# MusselGapeTracker_RevB.net
KiCad netlist of a schematic drawn in EAGLE
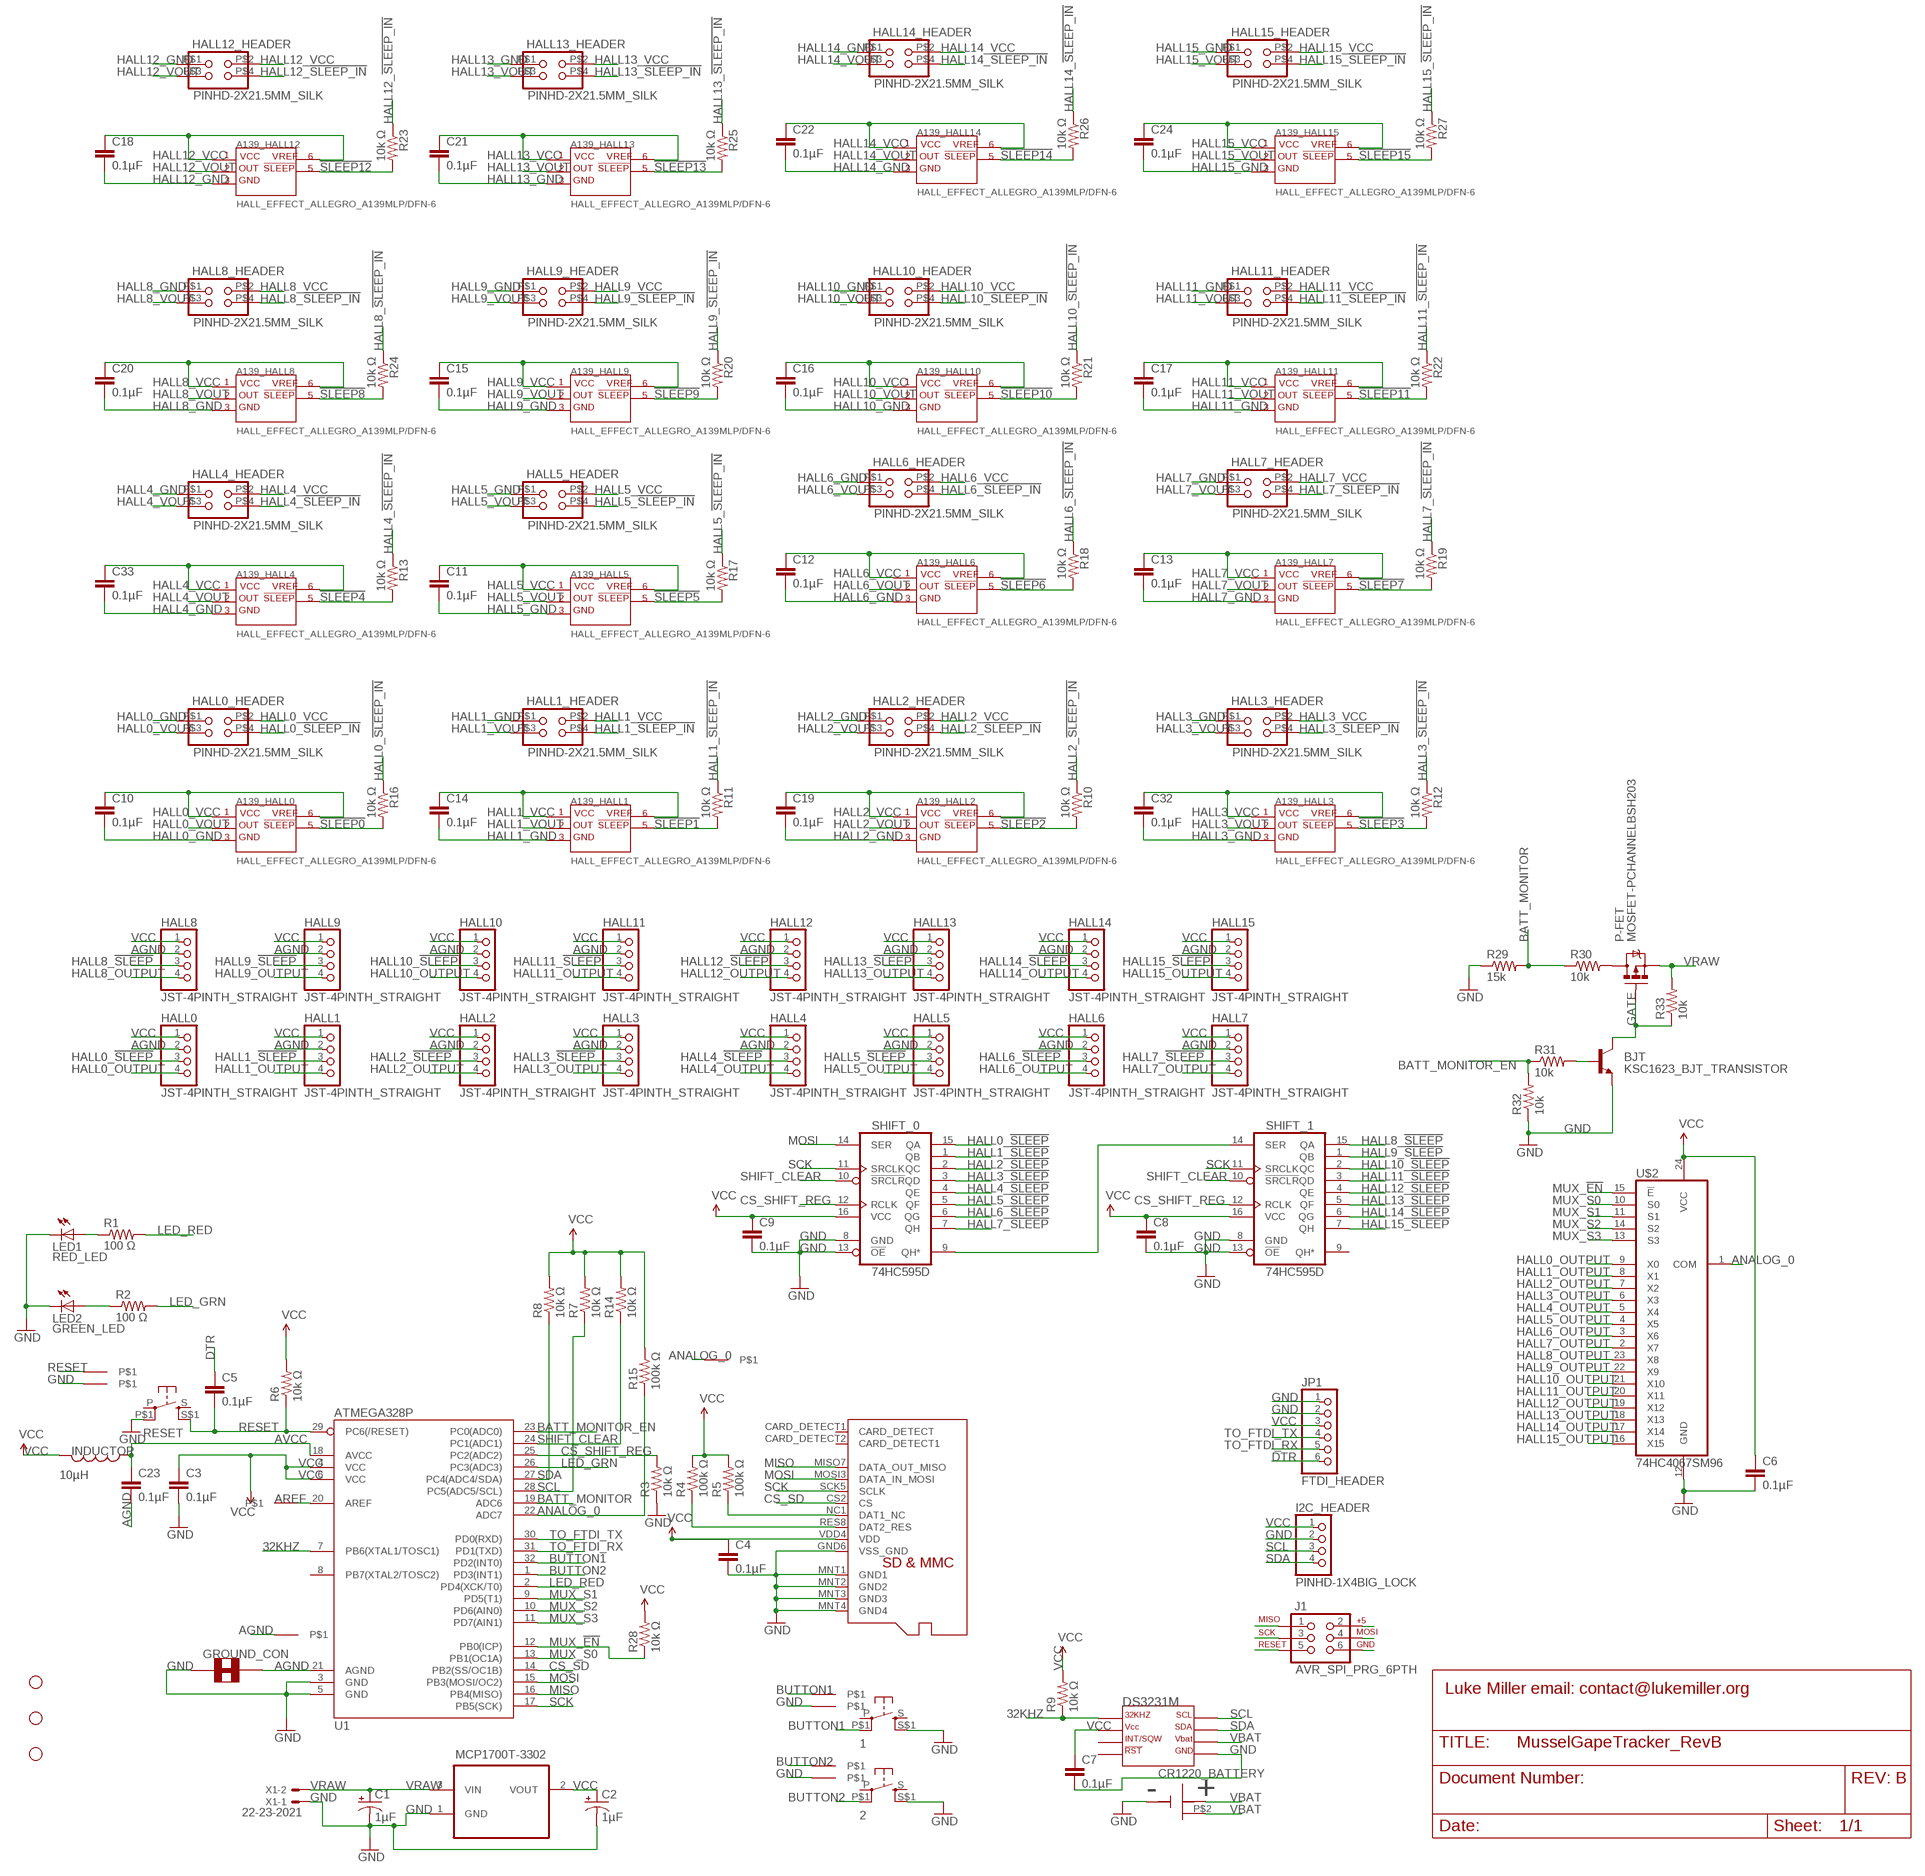
[diagram p0: schematic, sheet 1]

(export (version "E")
  (design (tool "Eeschema 10.0.6"))
  (components
    (comp (ref "1")
      (value "PUSHBUTTON_DPST_SMDSTANDARD")
      (footprint "eagle-import:PUSHBUTTON_DPST_SMD")
      (libsource (lib "eagle-import") (part "PUSHBUTTON_DPST_SMDSTANDARD"))
    )
    (comp (ref "2")
      (value "PUSHBUTTON_DPST_SMDSTANDARD")
      (footprint "eagle-import:PUSHBUTTON_DPST_SMD")
      (libsource (lib "eagle-import") (part "PUSHBUTTON_DPST_SMDSTANDARD"))
    )
    (comp (ref "A139_HALL0")
      (value "HALL_EFFECT_ALLEGRO_A139MLP/DFN-6")
      (footprint "eagle-import:A139__HALL_EFFECT")
      (libsource (lib "eagle-import") (part "HALL_EFFECT_ALLEGRO_A139MLP/DFN-6"))
    )
    (comp (ref "A139_HALL1")
      (value "HALL_EFFECT_ALLEGRO_A139MLP/DFN-6")
      (footprint "eagle-import:A139__HALL_EFFECT")
      (libsource (lib "eagle-import") (part "HALL_EFFECT_ALLEGRO_A139MLP/DFN-6"))
    )
    (comp (ref "A139_HALL2")
      (value "HALL_EFFECT_ALLEGRO_A139MLP/DFN-6")
      (footprint "eagle-import:A139__HALL_EFFECT")
      (libsource (lib "eagle-import") (part "HALL_EFFECT_ALLEGRO_A139MLP/DFN-6"))
    )
    (comp (ref "A139_HALL3")
      (value "HALL_EFFECT_ALLEGRO_A139MLP/DFN-6")
      (footprint "eagle-import:A139__HALL_EFFECT")
      (libsource (lib "eagle-import") (part "HALL_EFFECT_ALLEGRO_A139MLP/DFN-6"))
    )
    (comp (ref "A139_HALL4")
      (value "HALL_EFFECT_ALLEGRO_A139MLP/DFN-6")
      (footprint "eagle-import:A139__HALL_EFFECT")
      (libsource (lib "eagle-import") (part "HALL_EFFECT_ALLEGRO_A139MLP/DFN-6"))
    )
    (comp (ref "A139_HALL5")
      (value "HALL_EFFECT_ALLEGRO_A139MLP/DFN-6")
      (footprint "eagle-import:A139__HALL_EFFECT")
      (libsource (lib "eagle-import") (part "HALL_EFFECT_ALLEGRO_A139MLP/DFN-6"))
    )
    (comp (ref "A139_HALL6")
      (value "HALL_EFFECT_ALLEGRO_A139MLP/DFN-6")
      (footprint "eagle-import:A139__HALL_EFFECT")
      (libsource (lib "eagle-import") (part "HALL_EFFECT_ALLEGRO_A139MLP/DFN-6"))
    )
    (comp (ref "A139_HALL7")
      (value "HALL_EFFECT_ALLEGRO_A139MLP/DFN-6")
      (footprint "eagle-import:A139__HALL_EFFECT")
      (libsource (lib "eagle-import") (part "HALL_EFFECT_ALLEGRO_A139MLP/DFN-6"))
    )
    (comp (ref "A139_HALL8")
      (value "HALL_EFFECT_ALLEGRO_A139MLP/DFN-6")
      (footprint "eagle-import:A139__HALL_EFFECT")
      (libsource (lib "eagle-import") (part "HALL_EFFECT_ALLEGRO_A139MLP/DFN-6"))
    )
    (comp (ref "A139_HALL9")
      (value "HALL_EFFECT_ALLEGRO_A139MLP/DFN-6")
      (footprint "eagle-import:A139__HALL_EFFECT")
      (libsource (lib "eagle-import") (part "HALL_EFFECT_ALLEGRO_A139MLP/DFN-6"))
    )
    (comp (ref "A139_HALL10")
      (value "HALL_EFFECT_ALLEGRO_A139MLP/DFN-6")
      (footprint "eagle-import:A139__HALL_EFFECT")
      (libsource (lib "eagle-import") (part "HALL_EFFECT_ALLEGRO_A139MLP/DFN-6"))
    )
    (comp (ref "A139_HALL11")
      (value "HALL_EFFECT_ALLEGRO_A139MLP/DFN-6")
      (footprint "eagle-import:A139__HALL_EFFECT")
      (libsource (lib "eagle-import") (part "HALL_EFFECT_ALLEGRO_A139MLP/DFN-6"))
    )
    (comp (ref "A139_HALL12")
      (value "HALL_EFFECT_ALLEGRO_A139MLP/DFN-6")
      (footprint "eagle-import:A139__HALL_EFFECT")
      (libsource (lib "eagle-import") (part "HALL_EFFECT_ALLEGRO_A139MLP/DFN-6"))
    )
    (comp (ref "A139_HALL13")
      (value "HALL_EFFECT_ALLEGRO_A139MLP/DFN-6")
      (footprint "eagle-import:A139__HALL_EFFECT")
      (libsource (lib "eagle-import") (part "HALL_EFFECT_ALLEGRO_A139MLP/DFN-6"))
    )
    (comp (ref "A139_HALL14")
      (value "HALL_EFFECT_ALLEGRO_A139MLP/DFN-6")
      (footprint "eagle-import:A139__HALL_EFFECT")
      (libsource (lib "eagle-import") (part "HALL_EFFECT_ALLEGRO_A139MLP/DFN-6"))
    )
    (comp (ref "A139_HALL15")
      (value "HALL_EFFECT_ALLEGRO_A139MLP/DFN-6")
      (footprint "eagle-import:A139__HALL_EFFECT")
      (libsource (lib "eagle-import") (part "HALL_EFFECT_ALLEGRO_A139MLP/DFN-6"))
    )
    (comp (ref "BJT")
      (value "KSC1623_BJT_TRANSISTOR")
      (footprint "eagle-import:SOT23")
      (libsource (lib "eagle-import") (part "KSC1623_BJT_TRANSISTOR"))
    )
    (comp (ref "C1")
      (value "1µF")
      (footprint "eagle-import:PANASONIC_B")
      (libsource (lib "eagle-import") (part "CPOL-USB"))
    )
    (comp (ref "C2")
      (value "1µF")
      (footprint "eagle-import:PANASONIC_B")
      (libsource (lib "eagle-import") (part "CPOL-USB"))
    )
    (comp (ref "C3")
      (value "0.1µF")
      (footprint "eagle-import:0603")
      (libsource (lib "eagle-import") (part "CAP0603"))
    )
    (comp (ref "C4")
      (value "0.1µF")
      (footprint "eagle-import:0603")
      (libsource (lib "eagle-import") (part "CAP0603"))
    )
    (comp (ref "C5")
      (value "0.1µF")
      (footprint "eagle-import:0603")
      (libsource (lib "eagle-import") (part "CAP0603"))
    )
    (comp (ref "C6")
      (value "0.1µF")
      (footprint "eagle-import:0603")
      (libsource (lib "eagle-import") (part "CAP0603"))
    )
    (comp (ref "C7")
      (value "0.1µF")
      (footprint "eagle-import:0603")
      (libsource (lib "eagle-import") (part "CAP0603"))
    )
    (comp (ref "C8")
      (value "0.1µF")
      (footprint "eagle-import:0603")
      (libsource (lib "eagle-import") (part "CAP0603"))
    )
    (comp (ref "C9")
      (value "0.1µF")
      (footprint "eagle-import:0603")
      (libsource (lib "eagle-import") (part "CAP0603"))
    )
    (comp (ref "C10")
      (value "0.1µF")
      (footprint "eagle-import:0603")
      (libsource (lib "eagle-import") (part "CAP0603"))
    )
    (comp (ref "C11")
      (value "0.1µF")
      (footprint "eagle-import:0603")
      (libsource (lib "eagle-import") (part "CAP0603"))
    )
    (comp (ref "C12")
      (value "0.1µF")
      (footprint "eagle-import:0603")
      (libsource (lib "eagle-import") (part "CAP0603"))
    )
    (comp (ref "C13")
      (value "0.1µF")
      (footprint "eagle-import:0603")
      (libsource (lib "eagle-import") (part "CAP0603"))
    )
    (comp (ref "C14")
      (value "0.1µF")
      (footprint "eagle-import:0603")
      (libsource (lib "eagle-import") (part "CAP0603"))
    )
    (comp (ref "C15")
      (value "0.1µF")
      (footprint "eagle-import:0603")
      (libsource (lib "eagle-import") (part "CAP0603"))
    )
    (comp (ref "C16")
      (value "0.1µF")
      (footprint "eagle-import:0603")
      (libsource (lib "eagle-import") (part "CAP0603"))
    )
    (comp (ref "C17")
      (value "0.1µF")
      (footprint "eagle-import:0603")
      (libsource (lib "eagle-import") (part "CAP0603"))
    )
    (comp (ref "C18")
      (value "0.1µF")
      (footprint "eagle-import:0603")
      (libsource (lib "eagle-import") (part "CAP0603"))
    )
    (comp (ref "C19")
      (value "0.1µF")
      (footprint "eagle-import:0603")
      (libsource (lib "eagle-import") (part "CAP0603"))
    )
    (comp (ref "C20")
      (value "0.1µF")
      (footprint "eagle-import:0603")
      (libsource (lib "eagle-import") (part "CAP0603"))
    )
    (comp (ref "C21")
      (value "0.1µF")
      (footprint "eagle-import:0603")
      (libsource (lib "eagle-import") (part "CAP0603"))
    )
    (comp (ref "C22")
      (value "0.1µF")
      (footprint "eagle-import:0603")
      (libsource (lib "eagle-import") (part "CAP0603"))
    )
    (comp (ref "C23")
      (value "0.1µF")
      (footprint "eagle-import:0603")
      (libsource (lib "eagle-import") (part "CAP0603"))
    )
    (comp (ref "C24")
      (value "0.1µF")
      (footprint "eagle-import:0603")
      (libsource (lib "eagle-import") (part "CAP0603"))
    )
    (comp (ref "C32")
      (value "0.1µF")
      (footprint "eagle-import:0603")
      (libsource (lib "eagle-import") (part "CAP0603"))
    )
    (comp (ref "C33")
      (value "0.1µF")
      (footprint "eagle-import:0603")
      (libsource (lib "eagle-import") (part "CAP0603"))
    )
    (comp (ref "CR1220_BATTERY")
      (value "CR1220_BATTERY_HOLDERSMD")
      (footprint "eagle-import:CR1220_BATTERY_HOLDER_SMD")
      (libsource (lib "eagle-import") (part "CR1220_BATTERY_HOLDERSMD"))
    )
    (comp (ref "DS3231M")
      (value "DS3231MSOIC-8")
      (footprint "eagle-import:DS3231M_SOIC8")
      (libsource (lib "eagle-import") (part "DS3231MSOIC-8"))
    )
    (comp (ref "GROUND_CON")
      (value "SOLDER_JUMPER_TRACESTANDARD")
      (footprint "eagle-import:SJ_2S-TRACE")
      (libsource (lib "eagle-import") (part "SOLDER_JUMPER_TRACESTANDARD"))
    )
    (comp (ref "HALL0")
      (value "JST-4PINTH_STRAIGHT")
      (footprint "eagle-import:JST-PH-4-THM")
      (libsource (lib "eagle-import") (part "JST-4PINTH_STRAIGHT"))
    )
    (comp (ref "HALL0_HEADER")
      (value "PINHD-2X21.5MM_SILK")
      (footprint "eagle-import:2X2_1.5MM")
      (libsource (lib "eagle-import") (part "PINHD-2X21.5MM_SILK"))
    )
    (comp (ref "HALL1")
      (value "JST-4PINTH_STRAIGHT")
      (footprint "eagle-import:JST-PH-4-THM")
      (libsource (lib "eagle-import") (part "JST-4PINTH_STRAIGHT"))
    )
    (comp (ref "HALL1_HEADER")
      (value "PINHD-2X21.5MM_SILK")
      (footprint "eagle-import:2X2_1.5MM")
      (libsource (lib "eagle-import") (part "PINHD-2X21.5MM_SILK"))
    )
    (comp (ref "HALL2")
      (value "JST-4PINTH_STRAIGHT")
      (footprint "eagle-import:JST-PH-4-THM")
      (libsource (lib "eagle-import") (part "JST-4PINTH_STRAIGHT"))
    )
    (comp (ref "HALL2_HEADER")
      (value "PINHD-2X21.5MM_SILK")
      (footprint "eagle-import:2X2_1.5MM")
      (libsource (lib "eagle-import") (part "PINHD-2X21.5MM_SILK"))
    )
    (comp (ref "HALL3")
      (value "JST-4PINTH_STRAIGHT")
      (footprint "eagle-import:JST-PH-4-THM")
      (libsource (lib "eagle-import") (part "JST-4PINTH_STRAIGHT"))
    )
    (comp (ref "HALL3_HEADER")
      (value "PINHD-2X21.5MM_SILK")
      (footprint "eagle-import:2X2_1.5MM")
      (libsource (lib "eagle-import") (part "PINHD-2X21.5MM_SILK"))
    )
    (comp (ref "HALL4")
      (value "JST-4PINTH_STRAIGHT")
      (footprint "eagle-import:JST-PH-4-THM")
      (libsource (lib "eagle-import") (part "JST-4PINTH_STRAIGHT"))
    )
    (comp (ref "HALL4_HEADER")
      (value "PINHD-2X21.5MM_SILK")
      (footprint "eagle-import:2X2_1.5MM")
      (libsource (lib "eagle-import") (part "PINHD-2X21.5MM_SILK"))
    )
    (comp (ref "HALL5")
      (value "JST-4PINTH_STRAIGHT")
      (footprint "eagle-import:JST-PH-4-THM")
      (libsource (lib "eagle-import") (part "JST-4PINTH_STRAIGHT"))
    )
    (comp (ref "HALL5_HEADER")
      (value "PINHD-2X21.5MM_SILK")
      (footprint "eagle-import:2X2_1.5MM")
      (libsource (lib "eagle-import") (part "PINHD-2X21.5MM_SILK"))
    )
    (comp (ref "HALL6")
      (value "JST-4PINTH_STRAIGHT")
      (footprint "eagle-import:JST-PH-4-THM")
      (libsource (lib "eagle-import") (part "JST-4PINTH_STRAIGHT"))
    )
    (comp (ref "HALL6_HEADER")
      (value "PINHD-2X21.5MM_SILK")
      (footprint "eagle-import:2X2_1.5MM")
      (libsource (lib "eagle-import") (part "PINHD-2X21.5MM_SILK"))
    )
    (comp (ref "HALL7")
      (value "JST-4PINTH_STRAIGHT")
      (footprint "eagle-import:JST-PH-4-THM")
      (libsource (lib "eagle-import") (part "JST-4PINTH_STRAIGHT"))
    )
    (comp (ref "HALL7_HEADER")
      (value "PINHD-2X21.5MM_SILK")
      (footprint "eagle-import:2X2_1.5MM")
      (libsource (lib "eagle-import") (part "PINHD-2X21.5MM_SILK"))
    )
    (comp (ref "HALL8")
      (value "JST-4PINTH_STRAIGHT")
      (footprint "eagle-import:JST-PH-4-THM")
      (libsource (lib "eagle-import") (part "JST-4PINTH_STRAIGHT"))
    )
    (comp (ref "HALL8_HEADER")
      (value "PINHD-2X21.5MM_SILK")
      (footprint "eagle-import:2X2_1.5MM")
      (libsource (lib "eagle-import") (part "PINHD-2X21.5MM_SILK"))
    )
    (comp (ref "HALL9")
      (value "JST-4PINTH_STRAIGHT")
      (footprint "eagle-import:JST-PH-4-THM")
      (libsource (lib "eagle-import") (part "JST-4PINTH_STRAIGHT"))
    )
    (comp (ref "HALL9_HEADER")
      (value "PINHD-2X21.5MM_SILK")
      (footprint "eagle-import:2X2_1.5MM")
      (libsource (lib "eagle-import") (part "PINHD-2X21.5MM_SILK"))
    )
    (comp (ref "HALL10")
      (value "JST-4PINTH_STRAIGHT")
      (footprint "eagle-import:JST-PH-4-THM")
      (libsource (lib "eagle-import") (part "JST-4PINTH_STRAIGHT"))
    )
    (comp (ref "HALL10_HEADER")
      (value "PINHD-2X21.5MM_SILK")
      (footprint "eagle-import:2X2_1.5MM")
      (libsource (lib "eagle-import") (part "PINHD-2X21.5MM_SILK"))
    )
    (comp (ref "HALL11")
      (value "JST-4PINTH_STRAIGHT")
      (footprint "eagle-import:JST-PH-4-THM")
      (libsource (lib "eagle-import") (part "JST-4PINTH_STRAIGHT"))
    )
    (comp (ref "HALL11_HEADER")
      (value "PINHD-2X21.5MM_SILK")
      (footprint "eagle-import:2X2_1.5MM")
      (libsource (lib "eagle-import") (part "PINHD-2X21.5MM_SILK"))
    )
    (comp (ref "HALL12")
      (value "JST-4PINTH_STRAIGHT")
      (footprint "eagle-import:JST-PH-4-THM")
      (libsource (lib "eagle-import") (part "JST-4PINTH_STRAIGHT"))
    )
    (comp (ref "HALL12_HEADER")
      (value "PINHD-2X21.5MM_SILK")
      (footprint "eagle-import:2X2_1.5MM")
      (libsource (lib "eagle-import") (part "PINHD-2X21.5MM_SILK"))
    )
    (comp (ref "HALL13")
      (value "JST-4PINTH_STRAIGHT")
      (footprint "eagle-import:JST-PH-4-THM")
      (libsource (lib "eagle-import") (part "JST-4PINTH_STRAIGHT"))
    )
    (comp (ref "HALL13_HEADER")
      (value "PINHD-2X21.5MM_SILK")
      (footprint "eagle-import:2X2_1.5MM")
      (libsource (lib "eagle-import") (part "PINHD-2X21.5MM_SILK"))
    )
    (comp (ref "HALL14")
      (value "JST-4PINTH_STRAIGHT")
      (footprint "eagle-import:JST-PH-4-THM")
      (libsource (lib "eagle-import") (part "JST-4PINTH_STRAIGHT"))
    )
    (comp (ref "HALL14_HEADER")
      (value "PINHD-2X21.5MM_SILK")
      (footprint "eagle-import:2X2_1.5MM")
      (libsource (lib "eagle-import") (part "PINHD-2X21.5MM_SILK"))
    )
    (comp (ref "HALL15")
      (value "JST-4PINTH_STRAIGHT")
      (footprint "eagle-import:JST-PH-4-THM")
      (libsource (lib "eagle-import") (part "JST-4PINTH_STRAIGHT"))
    )
    (comp (ref "HALL15_HEADER")
      (value "PINHD-2X21.5MM_SILK")
      (footprint "eagle-import:2X2_1.5MM")
      (libsource (lib "eagle-import") (part "PINHD-2X21.5MM_SILK"))
    )
    (comp (ref "I2C_HEADER")
      (value "PINHD-1X4BIG_LOCK")
      (footprint "eagle-import:1X04_BIGLOCK")
      (libsource (lib "eagle-import") (part "PINHD-1X4BIG_LOCK"))
    )
    (comp (ref "INDUCTOR")
      (value "10µH")
      (footprint "eagle-import:I_0805")
      (libsource (lib "eagle-import") (part "INDUCTOR0805_TY"))
    )
    (comp (ref "J1")
      (value "AVR_SPI_PRG_6PTH")
      (footprint "eagle-import:2X3")
      (libsource (lib "eagle-import") (part "AVR_SPI_PRG_6PTH"))
    )
    (comp (ref "JP1")
      (value "FTDI_HEADER")
      (footprint "eagle-import:1X06-BIGLOCK")
      (libsource (lib "eagle-import") (part "PINHD-1X6LOCK"))
    )
    (comp (ref "LED1")
      (value "RED_LED")
      (footprint "eagle-import:CHIPLED_0805")
      (libsource (lib "eagle-import") (part "LED0805"))
    )
    (comp (ref "LED2")
      (value "GREEN_LED")
      (footprint "eagle-import:CHIPLED_0805")
      (libsource (lib "eagle-import") (part "LED0805"))
    )
    (comp (ref "MCP1700T-3302")
      (value "MCP1700T-3302E/TT")
      (footprint "eagle-import:SOT95P237X112-3N")
      (libsource (lib "eagle-import") (part "MCP1700T-3302E/TT"))
    )
    (comp (ref "P-FET")
      (value "MOSFET-PCHANNELBSH203")
      (footprint "eagle-import:SOT23-3")
      (libsource (lib "eagle-import") (part "MOSFET-PCHANNELBSH203"))
    )
    (comp (ref "R1")
      (value "100 Ω")
      (footprint "eagle-import:R0603")
      (libsource (lib "eagle-import") (part "RESISTOR_SMDR0603"))
    )
    (comp (ref "R2")
      (value "100 Ω")
      (footprint "eagle-import:R0603")
      (libsource (lib "eagle-import") (part "RESISTOR_SMDR0603"))
    )
    (comp (ref "R3")
      (value "10k Ω")
      (footprint "eagle-import:R0603")
      (libsource (lib "eagle-import") (part "RESISTOR_SMDR0603"))
    )
    (comp (ref "R4")
      (value "100k Ω")
      (footprint "eagle-import:R0603")
      (libsource (lib "eagle-import") (part "RESISTOR_SMDR0603"))
    )
    (comp (ref "R5")
      (value "100k Ω")
      (footprint "eagle-import:R0603")
      (libsource (lib "eagle-import") (part "RESISTOR_SMDR0603"))
    )
    (comp (ref "R6")
      (value "10k Ω")
      (footprint "eagle-import:R0603")
      (libsource (lib "eagle-import") (part "RESISTOR_SMDR0603"))
    )
    (comp (ref "R7")
      (value "10k Ω")
      (footprint "eagle-import:R0603")
      (libsource (lib "eagle-import") (part "RESISTOR_SMDR0603"))
    )
    (comp (ref "R8")
      (value "10k Ω")
      (footprint "eagle-import:R0603")
      (libsource (lib "eagle-import") (part "RESISTOR_SMDR0603"))
    )
    (comp (ref "R9")
      (value "10k Ω")
      (footprint "eagle-import:R0603")
      (libsource (lib "eagle-import") (part "RESISTOR_SMDR0603"))
    )
    (comp (ref "R10")
      (value "10k Ω")
      (footprint "eagle-import:R0603")
      (libsource (lib "eagle-import") (part "RESISTOR_SMDR0603"))
    )
    (comp (ref "R11")
      (value "10k Ω")
      (footprint "eagle-import:R0603")
      (libsource (lib "eagle-import") (part "RESISTOR_SMDR0603"))
    )
    (comp (ref "R12")
      (value "10k Ω")
      (footprint "eagle-import:R0603")
      (libsource (lib "eagle-import") (part "RESISTOR_SMDR0603"))
    )
    (comp (ref "R13")
      (value "10k Ω")
      (footprint "eagle-import:R0603")
      (libsource (lib "eagle-import") (part "RESISTOR_SMDR0603"))
    )
    (comp (ref "R14")
      (value "10k Ω")
      (footprint "eagle-import:R0603")
      (libsource (lib "eagle-import") (part "RESISTOR_SMDR0603"))
    )
    (comp (ref "R15")
      (value "100k Ω")
      (footprint "eagle-import:R0603")
      (libsource (lib "eagle-import") (part "RESISTOR_SMDR0603"))
    )
    (comp (ref "R16")
      (value "10k Ω")
      (footprint "eagle-import:R0603")
      (libsource (lib "eagle-import") (part "RESISTOR_SMDR0603"))
    )
    (comp (ref "R17")
      (value "10k Ω")
      (footprint "eagle-import:R0603")
      (libsource (lib "eagle-import") (part "RESISTOR_SMDR0603"))
    )
    (comp (ref "R18")
      (value "10k Ω")
      (footprint "eagle-import:R0603")
      (libsource (lib "eagle-import") (part "RESISTOR_SMDR0603"))
    )
    (comp (ref "R19")
      (value "10k Ω")
      (footprint "eagle-import:R0603")
      (libsource (lib "eagle-import") (part "RESISTOR_SMDR0603"))
    )
    (comp (ref "R20")
      (value "10k Ω")
      (footprint "eagle-import:R0603")
      (libsource (lib "eagle-import") (part "RESISTOR_SMDR0603"))
    )
    (comp (ref "R21")
      (value "10k Ω")
      (footprint "eagle-import:R0603")
      (libsource (lib "eagle-import") (part "RESISTOR_SMDR0603"))
    )
    (comp (ref "R22")
      (value "10k Ω")
      (footprint "eagle-import:R0603")
      (libsource (lib "eagle-import") (part "RESISTOR_SMDR0603"))
    )
    (comp (ref "R23")
      (value "10k Ω")
      (footprint "eagle-import:R0603")
      (libsource (lib "eagle-import") (part "RESISTOR_SMDR0603"))
    )
    (comp (ref "R24")
      (value "10k Ω")
      (footprint "eagle-import:R0603")
      (libsource (lib "eagle-import") (part "RESISTOR_SMDR0603"))
    )
    (comp (ref "R25")
      (value "10k Ω")
      (footprint "eagle-import:R0603")
      (libsource (lib "eagle-import") (part "RESISTOR_SMDR0603"))
    )
    (comp (ref "R26")
      (value "10k Ω")
      (footprint "eagle-import:R0603")
      (libsource (lib "eagle-import") (part "RESISTOR_SMDR0603"))
    )
    (comp (ref "R27")
      (value "10k Ω")
      (footprint "eagle-import:R0603")
      (libsource (lib "eagle-import") (part "RESISTOR_SMDR0603"))
    )
    (comp (ref "R28")
      (value "10k Ω")
      (footprint "eagle-import:R0603")
      (libsource (lib "eagle-import") (part "RESISTOR_SMDR0603"))
    )
    (comp (ref "R29")
      (value "15k")
      (footprint "eagle-import:R0603")
      (libsource (lib "eagle-import") (part "RESISTOR_SMDR0603"))
    )
    (comp (ref "R30")
      (value "10k")
      (footprint "eagle-import:R0603")
      (libsource (lib "eagle-import") (part "RESISTOR_SMDR0603"))
    )
    (comp (ref "R31")
      (value "10k")
      (footprint "eagle-import:R0603")
      (libsource (lib "eagle-import") (part "RESISTOR_SMDR0603"))
    )
    (comp (ref "R32")
      (value "10k")
      (footprint "eagle-import:R0603")
      (libsource (lib "eagle-import") (part "RESISTOR_SMDR0603"))
    )
    (comp (ref "R33")
      (value "10k")
      (footprint "eagle-import:R0603")
      (libsource (lib "eagle-import") (part "RESISTOR_SMDR0603"))
    )
    (comp (ref "RESET")
      (value "PUSHBUTTON_DPST_SMDSTANDARD")
      (footprint "eagle-import:PUSHBUTTON_DPST_SMD")
      (libsource (lib "eagle-import") (part "PUSHBUTTON_DPST_SMDSTANDARD"))
    )
    (comp (ref "SHIFT_0")
      (value "74HC595D")
      (footprint "eagle-import:SO16")
      (libsource (lib "eagle-import") (part "74HC595D"))
    )
    (comp (ref "SHIFT_1")
      (value "74HC595D")
      (footprint "eagle-import:SO16")
      (libsource (lib "eagle-import") (part "74HC595D"))
    )
    (comp (ref "STANDOFF1")
      (value "STAND-OFF")
      (footprint "eagle-import:STAND-OFF")
      (libsource (lib "eagle-import") (part "STAND-OFF"))
    )
    (comp (ref "STANDOFF2")
      (value "STAND-OFF")
      (footprint "eagle-import:STAND-OFF")
      (libsource (lib "eagle-import") (part "STAND-OFF"))
    )
    (comp (ref "STANDOFF3")
      (value "STAND-OFF")
      (footprint "eagle-import:STAND-OFF")
      (libsource (lib "eagle-import") (part "STAND-OFF"))
    )
    (comp (ref "U$1")
      (value "MICROSD_MOLEX_REVERSECURRENT")
      (footprint "eagle-import:MICROSD_SOCKET_MOLEX_REVERSEMOUNT")
      (libsource (lib "eagle-import") (part "MICROSD_MOLEX_REVERSECURRENT"))
    )
    (comp (ref "U$2")
      (value "74HC4067SM96")
      (footprint "eagle-import:SSOP24")
      (libsource (lib "eagle-import") (part "74HC4067SM96"))
    )
    (comp (ref "U$3")
      (value "PINHD-1X1SMALL")
      (footprint "eagle-import:1X01_SMALL")
      (libsource (lib "eagle-import") (part "PINHD-1X1SMALL"))
    )
    (comp (ref "U$4")
      (value "PINHD-1X1SMALL")
      (footprint "eagle-import:1X01_SMALL")
      (libsource (lib "eagle-import") (part "PINHD-1X1SMALL"))
    )
    (comp (ref "U$6")
      (value "PINHD-1X1SMALL")
      (footprint "eagle-import:1X01_SMALL")
      (libsource (lib "eagle-import") (part "PINHD-1X1SMALL"))
    )
    (comp (ref "U$7")
      (value "PINHD-1X1SMALL")
      (footprint "eagle-import:1X01_SMALL")
      (libsource (lib "eagle-import") (part "PINHD-1X1SMALL"))
    )
    (comp (ref "U$8")
      (value "PINHD-1X1SMALL")
      (footprint "eagle-import:1X01_SMALL")
      (libsource (lib "eagle-import") (part "PINHD-1X1SMALL"))
    )
    (comp (ref "U$9")
      (value "PINHD-1X1SMALL")
      (footprint "eagle-import:1X01_SMALL")
      (libsource (lib "eagle-import") (part "PINHD-1X1SMALL"))
    )
    (comp (ref "U$10")
      (value "PINHD-1X1SMALL")
      (footprint "eagle-import:1X01_SMALL")
      (libsource (lib "eagle-import") (part "PINHD-1X1SMALL"))
    )
    (comp (ref "U$11")
      (value "PINHD-1X1SMALL")
      (footprint "eagle-import:1X01_SMALL")
      (libsource (lib "eagle-import") (part "PINHD-1X1SMALL"))
    )
    (comp (ref "U$17")
      (value "PINHD-1X1SMALL")
      (footprint "eagle-import:1X01_SMALL")
      (libsource (lib "eagle-import") (part "PINHD-1X1SMALL"))
    )
    (comp (ref "U1")
      (value "ATMEGA328P")
      (footprint "eagle-import:TQFP32-08")
      (libsource (lib "eagle-import") (part "ATMEGA328_SMT"))
    )
    (comp (ref "X1")
      (value "22-23-2021")
      (footprint "eagle-import:22-23-2021")
      (fields (field (name "MF") "MOLEX"))
      (libsource (lib "eagle-import") (part "22-23-2021"))
    )
  )
  (nets
    (net (code "1") (name "/32KHZ") (class "Default")
      (node (ref "DS3231M") (pin "1") (pinfunction "P$1_32KHZ_1") (pintype "bidirectional"))
      (node (ref "R9") (pin "1") (pinfunction "1_1") (pintype "passive"))
      (node (ref "U1") (pin "7") (pinfunction "PB6(XTAL1/TOSC1)_7") (pintype "bidirectional"))
    )
    (net (code "2") (name "/AGND") (class "Default")
      (node (ref "C23") (pin "2") (pinfunction "2_2") (pintype "passive"))
      (node (ref "GROUND_CON") (pin "2") (pinfunction "P$2_2") (pintype "bidirectional"))
      (node (ref "HALL0") (pin "2") (pinfunction "2_2") (pintype "passive"))
      (node (ref "HALL1") (pin "2") (pinfunction "2_2") (pintype "passive"))
      (node (ref "HALL10") (pin "2") (pinfunction "2_2") (pintype "passive"))
      (node (ref "HALL11") (pin "2") (pinfunction "2_2") (pintype "passive"))
      (node (ref "HALL12") (pin "2") (pinfunction "2_2") (pintype "passive"))
      (node (ref "HALL13") (pin "2") (pinfunction "2_2") (pintype "passive"))
      (node (ref "HALL14") (pin "2") (pinfunction "2_2") (pintype "passive"))
      (node (ref "HALL15") (pin "2") (pinfunction "2_2") (pintype "passive"))
      (node (ref "HALL2") (pin "2") (pinfunction "2_2") (pintype "passive"))
      (node (ref "HALL3") (pin "2") (pinfunction "2_2") (pintype "passive"))
      (node (ref "HALL4") (pin "2") (pinfunction "2_2") (pintype "passive"))
      (node (ref "HALL5") (pin "2") (pinfunction "2_2") (pintype "passive"))
      (node (ref "HALL6") (pin "2") (pinfunction "2_2") (pintype "passive"))
      (node (ref "HALL7") (pin "2") (pinfunction "2_2") (pintype "passive"))
      (node (ref "HALL8") (pin "2") (pinfunction "2_2") (pintype "passive"))
      (node (ref "HALL9") (pin "2") (pinfunction "2_2") (pintype "passive"))
      (node (ref "U$11") (pin "1") (pinfunction "P$1_1") (pintype "bidirectional"))
      (node (ref "U1") (pin "21") (pinfunction "AGND_21") (pintype "bidirectional"))
    )
    (net (code "3") (name "/ANALOG_0") (class "Default")
      (node (ref "R15") (pin "1") (pinfunction "1_1") (pintype "passive"))
      (node (ref "U$10") (pin "1") (pinfunction "P$1_1") (pintype "bidirectional"))
      (node (ref "U$2") (pin "1") (pinfunction "COM_1") (pintype "output"))
      (node (ref "U1") (pin "22") (pinfunction "ADC7_22") (pintype "bidirectional"))
    )
    (net (code "4") (name "/AREF") (class "Default")
      (node (ref "U$17") (pin "1") (pinfunction "P$1_1") (pintype "bidirectional"))
      (node (ref "U1") (pin "20") (pinfunction "AREF_20") (pintype "bidirectional"))
    )
    (net (code "5") (name "/AVCC") (class "Default")
      (node (ref "C23") (pin "1") (pinfunction "1_1") (pintype "passive"))
      (node (ref "INDUCTOR") (pin "P$1") (pinfunction "1_P$1") (pintype "passive"))
      (node (ref "U1") (pin "18") (pinfunction "AVCC_18") (pintype "bidirectional"))
    )
    (net (code "6") (name "/BATT_MONITOR") (class "Default")
      (node (ref "R29") (pin "2") (pinfunction "2_2") (pintype "passive"))
      (node (ref "R30") (pin "1") (pinfunction "1_1") (pintype "passive"))
      (node (ref "U1") (pin "19") (pinfunction "ADC6_19") (pintype "bidirectional"))
    )
    (net (code "7") (name "/BATT_MONITOR_EN") (class "Default")
      (node (ref "R31") (pin "1") (pinfunction "1_1") (pintype "passive"))
      (node (ref "R32") (pin "2") (pinfunction "2_2") (pintype "passive"))
      (node (ref "U1") (pin "23") (pinfunction "PC0(ADC0)_23") (pintype "bidirectional"))
    )
    (net (code "8") (name "/BUTTON1") (class "Default")
      (node (ref "1") (pin "P$1") (pinfunction "P1_P$1") (pintype "passive"))
      (node (ref "U$6") (pin "1") (pinfunction "P$1_1") (pintype "bidirectional"))
      (node (ref "U1") (pin "32") (pinfunction "PD2(INT0)_32") (pintype "bidirectional"))
    )
    (net (code "9") (name "/BUTTON2") (class "Default")
      (node (ref "2") (pin "P$1") (pinfunction "P1_P$1") (pintype "passive"))
      (node (ref "U$8") (pin "1") (pinfunction "P$1_1") (pintype "bidirectional"))
      (node (ref "U1") (pin "1") (pinfunction "PD3(INT1)_1") (pintype "bidirectional"))
    )
    (net (code "10") (name "/CS_SD") (class "Default")
      (node (ref "U$1") (pin "CS2") (pinfunction "CS_CS2") (pintype "input"))
      (node (ref "U1") (pin "14") (pinfunction "PB2(SS/OC1B)_14") (pintype "bidirectional"))
    )
    (net (code "11") (name "/CS_SHIFT_REG") (class "Default")
      (node (ref "R3") (pin "2") (pinfunction "2_2") (pintype "passive"))
      (node (ref "SHIFT_0") (pin "12") (pinfunction "RCLK_12") (pintype "input"))
      (node (ref "SHIFT_1") (pin "12") (pinfunction "RCLK_12") (pintype "input"))
      (node (ref "U1") (pin "25") (pinfunction "PC2(ADC2)_25") (pintype "bidirectional"))
    )
    (net (code "12") (name "/DTR") (class "Default")
      (node (ref "C5") (pin "1") (pinfunction "1_1") (pintype "passive"))
      (node (ref "JP1") (pin "6") (pinfunction "6_6") (pintype "passive"))
    )
    (net (code "13") (name "/GATE") (class "Default")
      (node (ref "BJT") (pin "3") (pinfunction "C_3") (pintype "passive"))
      (node (ref "P-FET") (pin "1") (pinfunction "G_1") (pintype "passive"))
      (node (ref "R33") (pin "1") (pinfunction "1_1") (pintype "passive"))
    )
    (net (code "14") (name "/HALL0_GND") (class "Default")
      (node (ref "A139_HALL0") (pin "P$3_4") (pinfunction "P$3_P$3_4") (pintype "bidirectional"))
      (node (ref "C10") (pin "2") (pinfunction "2_2") (pintype "passive"))
      (node (ref "HALL0_HEADER") (pin "P$1") (pinfunction "1_P$1") (pintype "passive"))
    )
    (net (code "15") (name "/HALL0_OUTPUT") (class "Default")
      (node (ref "HALL0") (pin "4") (pinfunction "4_4") (pintype "passive"))
      (node (ref "U$2") (pin "9") (pinfunction "X0_9") (pintype "input"))
    )
    (net (code "16") (name "/HALL0_VCC") (class "Default")
      (node (ref "A139_HALL0") (pin "P$1") (pinfunction "P$1_P$1") (pintype "bidirectional"))
      (node (ref "A139_HALL0") (pin "P$6") (pinfunction "P$6_P$6") (pintype "bidirectional"))
      (node (ref "C10") (pin "1") (pinfunction "1_1") (pintype "passive"))
      (node (ref "HALL0_HEADER") (pin "P$2") (pinfunction "2_P$2") (pintype "passive"))
    )
    (net (code "17") (name "/HALL0_VOUT") (class "Default")
      (node (ref "A139_HALL0") (pin "P$2") (pinfunction "P$2_P$2") (pintype "bidirectional"))
      (node (ref "HALL0_HEADER") (pin "P$3") (pinfunction "3_P$3") (pintype "passive"))
    )
    (net (code "18") (name "/HALL0_~{SLEEP_IN}") (class "Default")
      (node (ref "HALL0_HEADER") (pin "P$4") (pinfunction "4_P$4") (pintype "passive"))
      (node (ref "R16") (pin "1") (pinfunction "1_1") (pintype "passive"))
    )
    (net (code "19") (name "/HALL0_~{SLEEP}") (class "Default")
      (node (ref "HALL0") (pin "3") (pinfunction "3_3") (pintype "passive"))
      (node (ref "SHIFT_0") (pin "15") (pinfunction "QA_15") (pintype "tri_state"))
    )
    (net (code "20") (name "/HALL1_GND") (class "Default")
      (node (ref "A139_HALL1") (pin "P$3_4") (pinfunction "P$3_P$3_4") (pintype "bidirectional"))
      (node (ref "C14") (pin "2") (pinfunction "2_2") (pintype "passive"))
      (node (ref "HALL1_HEADER") (pin "P$1") (pinfunction "1_P$1") (pintype "passive"))
    )
    (net (code "21") (name "/HALL1_OUTPUT") (class "Default")
      (node (ref "HALL1") (pin "4") (pinfunction "4_4") (pintype "passive"))
      (node (ref "U$2") (pin "8") (pinfunction "X1_8") (pintype "input"))
    )
    (net (code "22") (name "/HALL1_VCC") (class "Default")
      (node (ref "A139_HALL1") (pin "P$1") (pinfunction "P$1_P$1") (pintype "bidirectional"))
      (node (ref "A139_HALL1") (pin "P$6") (pinfunction "P$6_P$6") (pintype "bidirectional"))
      (node (ref "C14") (pin "1") (pinfunction "1_1") (pintype "passive"))
      (node (ref "HALL1_HEADER") (pin "P$2") (pinfunction "2_P$2") (pintype "passive"))
    )
    (net (code "23") (name "/HALL1_VOUT") (class "Default")
      (node (ref "A139_HALL1") (pin "P$2") (pinfunction "P$2_P$2") (pintype "bidirectional"))
      (node (ref "HALL1_HEADER") (pin "P$3") (pinfunction "3_P$3") (pintype "passive"))
    )
    (net (code "24") (name "/HALL1_~{SLEEP_IN}") (class "Default")
      (node (ref "HALL1_HEADER") (pin "P$4") (pinfunction "4_P$4") (pintype "passive"))
      (node (ref "R11") (pin "1") (pinfunction "1_1") (pintype "passive"))
    )
    (net (code "25") (name "/HALL1_~{SLEEP}") (class "Default")
      (node (ref "HALL1") (pin "3") (pinfunction "3_3") (pintype "passive"))
      (node (ref "SHIFT_0") (pin "1") (pinfunction "QB_1") (pintype "tri_state"))
    )
    (net (code "26") (name "/HALL2_GND") (class "Default")
      (node (ref "A139_HALL2") (pin "P$3_4") (pinfunction "P$3_P$3_4") (pintype "bidirectional"))
      (node (ref "C19") (pin "2") (pinfunction "2_2") (pintype "passive"))
      (node (ref "HALL2_HEADER") (pin "P$1") (pinfunction "1_P$1") (pintype "passive"))
    )
    (net (code "27") (name "/HALL2_OUTPUT") (class "Default")
      (node (ref "HALL2") (pin "4") (pinfunction "4_4") (pintype "passive"))
      (node (ref "U$2") (pin "7") (pinfunction "X2_7") (pintype "input"))
    )
    (net (code "28") (name "/HALL2_VCC") (class "Default")
      (node (ref "A139_HALL2") (pin "P$1") (pinfunction "P$1_P$1") (pintype "bidirectional"))
      (node (ref "A139_HALL2") (pin "P$6") (pinfunction "P$6_P$6") (pintype "bidirectional"))
      (node (ref "C19") (pin "1") (pinfunction "1_1") (pintype "passive"))
      (node (ref "HALL2_HEADER") (pin "P$2") (pinfunction "2_P$2") (pintype "passive"))
    )
    (net (code "29") (name "/HALL2_VOUT") (class "Default")
      (node (ref "A139_HALL2") (pin "P$2") (pinfunction "P$2_P$2") (pintype "bidirectional"))
      (node (ref "HALL2_HEADER") (pin "P$3") (pinfunction "3_P$3") (pintype "passive"))
    )
    (net (code "30") (name "/HALL2_~{SLEEP_IN}") (class "Default")
      (node (ref "HALL2_HEADER") (pin "P$4") (pinfunction "4_P$4") (pintype "passive"))
      (node (ref "R10") (pin "1") (pinfunction "1_1") (pintype "passive"))
    )
    (net (code "31") (name "/HALL2_~{SLEEP}") (class "Default")
      (node (ref "HALL2") (pin "3") (pinfunction "3_3") (pintype "passive"))
      (node (ref "SHIFT_0") (pin "2") (pinfunction "QC_2") (pintype "tri_state"))
    )
    (net (code "32") (name "/HALL3_GND") (class "Default")
      (node (ref "A139_HALL3") (pin "P$3_4") (pinfunction "P$3_P$3_4") (pintype "bidirectional"))
      (node (ref "C32") (pin "2") (pinfunction "2_2") (pintype "passive"))
      (node (ref "HALL3_HEADER") (pin "P$1") (pinfunction "1_P$1") (pintype "passive"))
    )
    (net (code "33") (name "/HALL3_OUTPUT") (class "Default")
      (node (ref "HALL3") (pin "4") (pinfunction "4_4") (pintype "passive"))
      (node (ref "U$2") (pin "6") (pinfunction "X3_6") (pintype "input"))
    )
    (net (code "34") (name "/HALL3_VCC") (class "Default")
      (node (ref "A139_HALL3") (pin "P$1") (pinfunction "P$1_P$1") (pintype "bidirectional"))
      (node (ref "A139_HALL3") (pin "P$6") (pinfunction "P$6_P$6") (pintype "bidirectional"))
      (node (ref "C32") (pin "1") (pinfunction "1_1") (pintype "passive"))
      (node (ref "HALL3_HEADER") (pin "P$2") (pinfunction "2_P$2") (pintype "passive"))
    )
    (net (code "35") (name "/HALL3_VOUT") (class "Default")
      (node (ref "A139_HALL3") (pin "P$2") (pinfunction "P$2_P$2") (pintype "bidirectional"))
      (node (ref "HALL3_HEADER") (pin "P$3") (pinfunction "3_P$3") (pintype "passive"))
    )
    (net (code "36") (name "/HALL3_~{SLEEP_IN}") (class "Default")
      (node (ref "HALL3_HEADER") (pin "P$4") (pinfunction "4_P$4") (pintype "passive"))
      (node (ref "R12") (pin "1") (pinfunction "1_1") (pintype "passive"))
    )
    (net (code "37") (name "/HALL3_~{SLEEP}") (class "Default")
      (node (ref "HALL3") (pin "3") (pinfunction "3_3") (pintype "passive"))
      (node (ref "SHIFT_0") (pin "3") (pinfunction "QD_3") (pintype "tri_state"))
    )
    (net (code "38") (name "/HALL4_GND") (class "Default")
      (node (ref "A139_HALL4") (pin "P$3_4") (pinfunction "P$3_P$3_4") (pintype "bidirectional"))
      (node (ref "C33") (pin "2") (pinfunction "2_2") (pintype "passive"))
      (node (ref "HALL4_HEADER") (pin "P$1") (pinfunction "1_P$1") (pintype "passive"))
    )
    (net (code "39") (name "/HALL4_OUTPUT") (class "Default")
      (node (ref "HALL4") (pin "4") (pinfunction "4_4") (pintype "passive"))
      (node (ref "U$2") (pin "5") (pinfunction "X4_5") (pintype "input"))
    )
    (net (code "40") (name "/HALL4_VCC") (class "Default")
      (node (ref "A139_HALL4") (pin "P$1") (pinfunction "P$1_P$1") (pintype "bidirectional"))
      (node (ref "A139_HALL4") (pin "P$6") (pinfunction "P$6_P$6") (pintype "bidirectional"))
      (node (ref "C33") (pin "1") (pinfunction "1_1") (pintype "passive"))
      (node (ref "HALL4_HEADER") (pin "P$2") (pinfunction "2_P$2") (pintype "passive"))
    )
    (net (code "41") (name "/HALL4_VOUT") (class "Default")
      (node (ref "A139_HALL4") (pin "P$2") (pinfunction "P$2_P$2") (pintype "bidirectional"))
      (node (ref "HALL4_HEADER") (pin "P$3") (pinfunction "3_P$3") (pintype "passive"))
    )
    (net (code "42") (name "/HALL4_~{SLEEP_IN}") (class "Default")
      (node (ref "HALL4_HEADER") (pin "P$4") (pinfunction "4_P$4") (pintype "passive"))
      (node (ref "R13") (pin "1") (pinfunction "1_1") (pintype "passive"))
    )
    (net (code "43") (name "/HALL4_~{SLEEP}") (class "Default")
      (node (ref "HALL4") (pin "3") (pinfunction "3_3") (pintype "passive"))
      (node (ref "SHIFT_0") (pin "4") (pinfunction "QE_4") (pintype "tri_state"))
    )
    (net (code "44") (name "/HALL5_GND") (class "Default")
      (node (ref "A139_HALL5") (pin "P$3_4") (pinfunction "P$3_P$3_4") (pintype "bidirectional"))
      (node (ref "C11") (pin "2") (pinfunction "2_2") (pintype "passive"))
      (node (ref "HALL5_HEADER") (pin "P$1") (pinfunction "1_P$1") (pintype "passive"))
    )
    (net (code "45") (name "/HALL5_OUTPUT") (class "Default")
      (node (ref "HALL5") (pin "4") (pinfunction "4_4") (pintype "passive"))
      (node (ref "U$2") (pin "4") (pinfunction "X5_4") (pintype "input"))
    )
    (net (code "46") (name "/HALL5_VCC") (class "Default")
      (node (ref "A139_HALL5") (pin "P$1") (pinfunction "P$1_P$1") (pintype "bidirectional"))
      (node (ref "A139_HALL5") (pin "P$6") (pinfunction "P$6_P$6") (pintype "bidirectional"))
      (node (ref "C11") (pin "1") (pinfunction "1_1") (pintype "passive"))
      (node (ref "HALL5_HEADER") (pin "P$2") (pinfunction "2_P$2") (pintype "passive"))
    )
    (net (code "47") (name "/HALL5_VOUT") (class "Default")
      (node (ref "A139_HALL5") (pin "P$2") (pinfunction "P$2_P$2") (pintype "bidirectional"))
      (node (ref "HALL5_HEADER") (pin "P$3") (pinfunction "3_P$3") (pintype "passive"))
    )
    (net (code "48") (name "/HALL5_~{SLEEP_IN}") (class "Default")
      (node (ref "HALL5_HEADER") (pin "P$4") (pinfunction "4_P$4") (pintype "passive"))
      (node (ref "R17") (pin "1") (pinfunction "1_1") (pintype "passive"))
    )
    (net (code "49") (name "/HALL5_~{SLEEP}") (class "Default")
      (node (ref "HALL5") (pin "3") (pinfunction "3_3") (pintype "passive"))
      (node (ref "SHIFT_0") (pin "5") (pinfunction "QF_5") (pintype "tri_state"))
    )
    (net (code "50") (name "/HALL6_GND") (class "Default")
      (node (ref "A139_HALL6") (pin "P$3_4") (pinfunction "P$3_P$3_4") (pintype "bidirectional"))
      (node (ref "C12") (pin "2") (pinfunction "2_2") (pintype "passive"))
      (node (ref "HALL6_HEADER") (pin "P$1") (pinfunction "1_P$1") (pintype "passive"))
    )
    (net (code "51") (name "/HALL6_OUTPUT") (class "Default")
      (node (ref "HALL6") (pin "4") (pinfunction "4_4") (pintype "passive"))
      (node (ref "U$2") (pin "3") (pinfunction "X6_3") (pintype "input"))
    )
    (net (code "52") (name "/HALL6_VCC") (class "Default")
      (node (ref "A139_HALL6") (pin "P$1") (pinfunction "P$1_P$1") (pintype "bidirectional"))
      (node (ref "A139_HALL6") (pin "P$6") (pinfunction "P$6_P$6") (pintype "bidirectional"))
      (node (ref "C12") (pin "1") (pinfunction "1_1") (pintype "passive"))
      (node (ref "HALL6_HEADER") (pin "P$2") (pinfunction "2_P$2") (pintype "passive"))
    )
    (net (code "53") (name "/HALL6_VOUT") (class "Default")
      (node (ref "A139_HALL6") (pin "P$2") (pinfunction "P$2_P$2") (pintype "bidirectional"))
      (node (ref "HALL6_HEADER") (pin "P$3") (pinfunction "3_P$3") (pintype "passive"))
    )
    (net (code "54") (name "/HALL6_~{SLEEP_IN}") (class "Default")
      (node (ref "HALL6_HEADER") (pin "P$4") (pinfunction "4_P$4") (pintype "passive"))
      (node (ref "R18") (pin "1") (pinfunction "1_1") (pintype "passive"))
    )
    (net (code "55") (name "/HALL6_~{SLEEP}") (class "Default")
      (node (ref "HALL6") (pin "3") (pinfunction "3_3") (pintype "passive"))
      (node (ref "SHIFT_0") (pin "6") (pinfunction "QG_6") (pintype "tri_state"))
    )
    (net (code "56") (name "/HALL7_GND") (class "Default")
      (node (ref "A139_HALL7") (pin "P$3_4") (pinfunction "P$3_P$3_4") (pintype "bidirectional"))
      (node (ref "C13") (pin "2") (pinfunction "2_2") (pintype "passive"))
      (node (ref "HALL7_HEADER") (pin "P$1") (pinfunction "1_P$1") (pintype "passive"))
    )
    (net (code "57") (name "/HALL7_OUTPUT") (class "Default")
      (node (ref "HALL7") (pin "4") (pinfunction "4_4") (pintype "passive"))
      (node (ref "U$2") (pin "2") (pinfunction "X7_2") (pintype "input"))
    )
    (net (code "58") (name "/HALL7_VCC") (class "Default")
      (node (ref "A139_HALL7") (pin "P$1") (pinfunction "P$1_P$1") (pintype "bidirectional"))
      (node (ref "A139_HALL7") (pin "P$6") (pinfunction "P$6_P$6") (pintype "bidirectional"))
      (node (ref "C13") (pin "1") (pinfunction "1_1") (pintype "passive"))
      (node (ref "HALL7_HEADER") (pin "P$2") (pinfunction "2_P$2") (pintype "passive"))
    )
    (net (code "59") (name "/HALL7_VOUT") (class "Default")
      (node (ref "A139_HALL7") (pin "P$2") (pinfunction "P$2_P$2") (pintype "bidirectional"))
      (node (ref "HALL7_HEADER") (pin "P$3") (pinfunction "3_P$3") (pintype "passive"))
    )
    (net (code "60") (name "/HALL7_~{SLEEP_IN}") (class "Default")
      (node (ref "HALL7_HEADER") (pin "P$4") (pinfunction "4_P$4") (pintype "passive"))
      (node (ref "R19") (pin "1") (pinfunction "1_1") (pintype "passive"))
    )
    (net (code "61") (name "/HALL7_~{SLEEP}") (class "Default")
      (node (ref "HALL7") (pin "3") (pinfunction "3_3") (pintype "passive"))
      (node (ref "SHIFT_0") (pin "7") (pinfunction "QH_7") (pintype "tri_state"))
    )
    (net (code "62") (name "/HALL8_GND") (class "Default")
      (node (ref "A139_HALL8") (pin "P$3_4") (pinfunction "P$3_P$3_4") (pintype "bidirectional"))
      (node (ref "C20") (pin "2") (pinfunction "2_2") (pintype "passive"))
      (node (ref "HALL8_HEADER") (pin "P$1") (pinfunction "1_P$1") (pintype "passive"))
    )
    (net (code "63") (name "/HALL8_OUTPUT") (class "Default")
      (node (ref "HALL8") (pin "4") (pinfunction "4_4") (pintype "passive"))
      (node (ref "U$2") (pin "23") (pinfunction "X8_23") (pintype "input"))
    )
    (net (code "64") (name "/HALL8_VCC") (class "Default")
      (node (ref "A139_HALL8") (pin "P$1") (pinfunction "P$1_P$1") (pintype "bidirectional"))
      (node (ref "A139_HALL8") (pin "P$6") (pinfunction "P$6_P$6") (pintype "bidirectional"))
      (node (ref "C20") (pin "1") (pinfunction "1_1") (pintype "passive"))
      (node (ref "HALL8_HEADER") (pin "P$2") (pinfunction "2_P$2") (pintype "passive"))
    )
    (net (code "65") (name "/HALL8_VOUT") (class "Default")
      (node (ref "A139_HALL8") (pin "P$2") (pinfunction "P$2_P$2") (pintype "bidirectional"))
      (node (ref "HALL8_HEADER") (pin "P$3") (pinfunction "3_P$3") (pintype "passive"))
    )
    (net (code "66") (name "/HALL8_~{SLEEP_IN}") (class "Default")
      (node (ref "HALL8_HEADER") (pin "P$4") (pinfunction "4_P$4") (pintype "passive"))
      (node (ref "R24") (pin "1") (pinfunction "1_1") (pintype "passive"))
    )
    (net (code "67") (name "/HALL8_~{SLEEP}") (class "Default")
      (node (ref "HALL8") (pin "3") (pinfunction "3_3") (pintype "passive"))
      (node (ref "SHIFT_1") (pin "15") (pinfunction "QA_15") (pintype "tri_state"))
    )
    (net (code "68") (name "/HALL9_GND") (class "Default")
      (node (ref "A139_HALL9") (pin "P$3_4") (pinfunction "P$3_P$3_4") (pintype "bidirectional"))
      (node (ref "C15") (pin "2") (pinfunction "2_2") (pintype "passive"))
      (node (ref "HALL9_HEADER") (pin "P$1") (pinfunction "1_P$1") (pintype "passive"))
    )
    (net (code "69") (name "/HALL9_OUTPUT") (class "Default")
      (node (ref "HALL9") (pin "4") (pinfunction "4_4") (pintype "passive"))
      (node (ref "U$2") (pin "22") (pinfunction "X9_22") (pintype "input"))
    )
    (net (code "70") (name "/HALL9_VCC") (class "Default")
      (node (ref "A139_HALL9") (pin "P$1") (pinfunction "P$1_P$1") (pintype "bidirectional"))
      (node (ref "A139_HALL9") (pin "P$6") (pinfunction "P$6_P$6") (pintype "bidirectional"))
      (node (ref "C15") (pin "1") (pinfunction "1_1") (pintype "passive"))
      (node (ref "HALL9_HEADER") (pin "P$2") (pinfunction "2_P$2") (pintype "passive"))
    )
    (net (code "71") (name "/HALL9_VOUT") (class "Default")
      (node (ref "A139_HALL9") (pin "P$2") (pinfunction "P$2_P$2") (pintype "bidirectional"))
      (node (ref "HALL9_HEADER") (pin "P$3") (pinfunction "3_P$3") (pintype "passive"))
    )
    (net (code "72") (name "/HALL9_~{SLEEP_IN}") (class "Default")
      (node (ref "HALL9_HEADER") (pin "P$4") (pinfunction "4_P$4") (pintype "passive"))
      (node (ref "R20") (pin "1") (pinfunction "1_1") (pintype "passive"))
    )
    (net (code "73") (name "/HALL9_~{SLEEP}") (class "Default")
      (node (ref "HALL9") (pin "3") (pinfunction "3_3") (pintype "passive"))
      (node (ref "SHIFT_1") (pin "1") (pinfunction "QB_1") (pintype "tri_state"))
    )
    (net (code "74") (name "/HALL10_GND") (class "Default")
      (node (ref "A139_HALL10") (pin "P$3_4") (pinfunction "P$3_P$3_4") (pintype "bidirectional"))
      (node (ref "C16") (pin "2") (pinfunction "2_2") (pintype "passive"))
      (node (ref "HALL10_HEADER") (pin "P$1") (pinfunction "1_P$1") (pintype "passive"))
    )
    (net (code "75") (name "/HALL10_OUTPUT") (class "Default")
      (node (ref "HALL10") (pin "4") (pinfunction "4_4") (pintype "passive"))
      (node (ref "U$2") (pin "21") (pinfunction "X10_21") (pintype "input"))
    )
    (net (code "76") (name "/HALL10_VCC") (class "Default")
      (node (ref "A139_HALL10") (pin "P$1") (pinfunction "P$1_P$1") (pintype "bidirectional"))
      (node (ref "A139_HALL10") (pin "P$6") (pinfunction "P$6_P$6") (pintype "bidirectional"))
      (node (ref "C16") (pin "1") (pinfunction "1_1") (pintype "passive"))
      (node (ref "HALL10_HEADER") (pin "P$2") (pinfunction "2_P$2") (pintype "passive"))
    )
    (net (code "77") (name "/HALL10_VOUT") (class "Default")
      (node (ref "A139_HALL10") (pin "P$2") (pinfunction "P$2_P$2") (pintype "bidirectional"))
      (node (ref "HALL10_HEADER") (pin "P$3") (pinfunction "3_P$3") (pintype "passive"))
    )
    (net (code "78") (name "/HALL10_~{SLEEP_IN}") (class "Default")
      (node (ref "HALL10_HEADER") (pin "P$4") (pinfunction "4_P$4") (pintype "passive"))
      (node (ref "R21") (pin "1") (pinfunction "1_1") (pintype "passive"))
    )
    (net (code "79") (name "/HALL10_~{SLEEP}") (class "Default")
      (node (ref "HALL10") (pin "3") (pinfunction "3_3") (pintype "passive"))
      (node (ref "SHIFT_1") (pin "2") (pinfunction "QC_2") (pintype "tri_state"))
    )
    (net (code "80") (name "/HALL11_GND") (class "Default")
      (node (ref "A139_HALL11") (pin "P$3_4") (pinfunction "P$3_P$3_4") (pintype "bidirectional"))
      (node (ref "C17") (pin "2") (pinfunction "2_2") (pintype "passive"))
      (node (ref "HALL11_HEADER") (pin "P$1") (pinfunction "1_P$1") (pintype "passive"))
    )
    (net (code "81") (name "/HALL11_OUTPUT") (class "Default")
      (node (ref "HALL11") (pin "4") (pinfunction "4_4") (pintype "passive"))
      (node (ref "U$2") (pin "20") (pinfunction "X11_20") (pintype "input"))
    )
    (net (code "82") (name "/HALL11_VCC") (class "Default")
      (node (ref "A139_HALL11") (pin "P$1") (pinfunction "P$1_P$1") (pintype "bidirectional"))
      (node (ref "A139_HALL11") (pin "P$6") (pinfunction "P$6_P$6") (pintype "bidirectional"))
      (node (ref "C17") (pin "1") (pinfunction "1_1") (pintype "passive"))
      (node (ref "HALL11_HEADER") (pin "P$2") (pinfunction "2_P$2") (pintype "passive"))
    )
    (net (code "83") (name "/HALL11_VOUT") (class "Default")
      (node (ref "A139_HALL11") (pin "P$2") (pinfunction "P$2_P$2") (pintype "bidirectional"))
      (node (ref "HALL11_HEADER") (pin "P$3") (pinfunction "3_P$3") (pintype "passive"))
    )
    (net (code "84") (name "/HALL11_~{SLEEP_IN}") (class "Default")
      (node (ref "HALL11_HEADER") (pin "P$4") (pinfunction "4_P$4") (pintype "passive"))
      (node (ref "R22") (pin "1") (pinfunction "1_1") (pintype "passive"))
    )
    (net (code "85") (name "/HALL11_~{SLEEP}") (class "Default")
      (node (ref "HALL11") (pin "3") (pinfunction "3_3") (pintype "passive"))
      (node (ref "SHIFT_1") (pin "3") (pinfunction "QD_3") (pintype "tri_state"))
    )
    (net (code "86") (name "/HALL12_GND") (class "Default")
      (node (ref "A139_HALL12") (pin "P$3_4") (pinfunction "P$3_P$3_4") (pintype "bidirectional"))
      (node (ref "C18") (pin "2") (pinfunction "2_2") (pintype "passive"))
      (node (ref "HALL12_HEADER") (pin "P$1") (pinfunction "1_P$1") (pintype "passive"))
    )
    (net (code "87") (name "/HALL12_OUTPUT") (class "Default")
      (node (ref "HALL12") (pin "4") (pinfunction "4_4") (pintype "passive"))
      (node (ref "U$2") (pin "19") (pinfunction "X12_19") (pintype "input"))
    )
    (net (code "88") (name "/HALL12_VCC") (class "Default")
      (node (ref "A139_HALL12") (pin "P$1") (pinfunction "P$1_P$1") (pintype "bidirectional"))
      (node (ref "A139_HALL12") (pin "P$6") (pinfunction "P$6_P$6") (pintype "bidirectional"))
      (node (ref "C18") (pin "1") (pinfunction "1_1") (pintype "passive"))
      (node (ref "HALL12_HEADER") (pin "P$2") (pinfunction "2_P$2") (pintype "passive"))
    )
    (net (code "89") (name "/HALL12_VOUT") (class "Default")
      (node (ref "A139_HALL12") (pin "P$2") (pinfunction "P$2_P$2") (pintype "bidirectional"))
      (node (ref "HALL12_HEADER") (pin "P$3") (pinfunction "3_P$3") (pintype "passive"))
    )
    (net (code "90") (name "/HALL12_~{SLEEP_IN}") (class "Default")
      (node (ref "HALL12_HEADER") (pin "P$4") (pinfunction "4_P$4") (pintype "passive"))
      (node (ref "R23") (pin "1") (pinfunction "1_1") (pintype "passive"))
    )
    (net (code "91") (name "/HALL12_~{SLEEP}") (class "Default")
      (node (ref "HALL12") (pin "3") (pinfunction "3_3") (pintype "passive"))
      (node (ref "SHIFT_1") (pin "4") (pinfunction "QE_4") (pintype "tri_state"))
    )
    (net (code "92") (name "/HALL13_GND") (class "Default")
      (node (ref "A139_HALL13") (pin "P$3_4") (pinfunction "P$3_P$3_4") (pintype "bidirectional"))
      (node (ref "C21") (pin "2") (pinfunction "2_2") (pintype "passive"))
      (node (ref "HALL13_HEADER") (pin "P$1") (pinfunction "1_P$1") (pintype "passive"))
    )
    (net (code "93") (name "/HALL13_OUTPUT") (class "Default")
      (node (ref "HALL13") (pin "4") (pinfunction "4_4") (pintype "passive"))
      (node (ref "U$2") (pin "18") (pinfunction "X13_18") (pintype "input"))
    )
    (net (code "94") (name "/HALL13_VCC") (class "Default")
      (node (ref "A139_HALL13") (pin "P$1") (pinfunction "P$1_P$1") (pintype "bidirectional"))
      (node (ref "A139_HALL13") (pin "P$6") (pinfunction "P$6_P$6") (pintype "bidirectional"))
      (node (ref "C21") (pin "1") (pinfunction "1_1") (pintype "passive"))
      (node (ref "HALL13_HEADER") (pin "P$2") (pinfunction "2_P$2") (pintype "passive"))
    )
    (net (code "95") (name "/HALL13_VOUT") (class "Default")
      (node (ref "A139_HALL13") (pin "P$2") (pinfunction "P$2_P$2") (pintype "bidirectional"))
      (node (ref "HALL13_HEADER") (pin "P$3") (pinfunction "3_P$3") (pintype "passive"))
    )
    (net (code "96") (name "/HALL13_~{SLEEP_IN}") (class "Default")
      (node (ref "HALL13_HEADER") (pin "P$4") (pinfunction "4_P$4") (pintype "passive"))
      (node (ref "R25") (pin "1") (pinfunction "1_1") (pintype "passive"))
    )
    (net (code "97") (name "/HALL13_~{SLEEP}") (class "Default")
      (node (ref "HALL13") (pin "3") (pinfunction "3_3") (pintype "passive"))
      (node (ref "SHIFT_1") (pin "5") (pinfunction "QF_5") (pintype "tri_state"))
    )
    (net (code "98") (name "/HALL14_GND") (class "Default")
      (node (ref "A139_HALL14") (pin "P$3_4") (pinfunction "P$3_P$3_4") (pintype "bidirectional"))
      (node (ref "C22") (pin "2") (pinfunction "2_2") (pintype "passive"))
      (node (ref "HALL14_HEADER") (pin "P$1") (pinfunction "1_P$1") (pintype "passive"))
    )
    (net (code "99") (name "/HALL14_OUTPUT") (class "Default")
      (node (ref "HALL14") (pin "4") (pinfunction "4_4") (pintype "passive"))
      (node (ref "U$2") (pin "17") (pinfunction "X14_17") (pintype "input"))
    )
    (net (code "100") (name "/HALL14_VCC") (class "Default")
      (node (ref "A139_HALL14") (pin "P$1") (pinfunction "P$1_P$1") (pintype "bidirectional"))
      (node (ref "A139_HALL14") (pin "P$6") (pinfunction "P$6_P$6") (pintype "bidirectional"))
      (node (ref "C22") (pin "1") (pinfunction "1_1") (pintype "passive"))
      (node (ref "HALL14_HEADER") (pin "P$2") (pinfunction "2_P$2") (pintype "passive"))
    )
    (net (code "101") (name "/HALL14_VOUT") (class "Default")
      (node (ref "A139_HALL14") (pin "P$2") (pinfunction "P$2_P$2") (pintype "bidirectional"))
      (node (ref "HALL14_HEADER") (pin "P$3") (pinfunction "3_P$3") (pintype "passive"))
    )
    (net (code "102") (name "/HALL14_~{SLEEP_IN}") (class "Default")
      (node (ref "HALL14_HEADER") (pin "P$4") (pinfunction "4_P$4") (pintype "passive"))
      (node (ref "R26") (pin "1") (pinfunction "1_1") (pintype "passive"))
    )
    (net (code "103") (name "/HALL14_~{SLEEP}") (class "Default")
      (node (ref "HALL14") (pin "3") (pinfunction "3_3") (pintype "passive"))
      (node (ref "SHIFT_1") (pin "6") (pinfunction "QG_6") (pintype "tri_state"))
    )
    (net (code "104") (name "/HALL15_GND") (class "Default")
      (node (ref "A139_HALL15") (pin "P$3_4") (pinfunction "P$3_P$3_4") (pintype "bidirectional"))
      (node (ref "C24") (pin "2") (pinfunction "2_2") (pintype "passive"))
      (node (ref "HALL15_HEADER") (pin "P$1") (pinfunction "1_P$1") (pintype "passive"))
    )
    (net (code "105") (name "/HALL15_OUTPUT") (class "Default")
      (node (ref "HALL15") (pin "4") (pinfunction "4_4") (pintype "passive"))
      (node (ref "U$2") (pin "16") (pinfunction "X15_16") (pintype "input"))
    )
    (net (code "106") (name "/HALL15_VCC") (class "Default")
      (node (ref "A139_HALL15") (pin "P$1") (pinfunction "P$1_P$1") (pintype "bidirectional"))
      (node (ref "A139_HALL15") (pin "P$6") (pinfunction "P$6_P$6") (pintype "bidirectional"))
      (node (ref "C24") (pin "1") (pinfunction "1_1") (pintype "passive"))
      (node (ref "HALL15_HEADER") (pin "P$2") (pinfunction "2_P$2") (pintype "passive"))
    )
    (net (code "107") (name "/HALL15_VOUT") (class "Default")
      (node (ref "A139_HALL15") (pin "P$2") (pinfunction "P$2_P$2") (pintype "bidirectional"))
      (node (ref "HALL15_HEADER") (pin "P$3") (pinfunction "3_P$3") (pintype "passive"))
    )
    (net (code "108") (name "/HALL15_~{SLEEP_IN}") (class "Default")
      (node (ref "HALL15_HEADER") (pin "P$4") (pinfunction "4_P$4") (pintype "passive"))
      (node (ref "R27") (pin "1") (pinfunction "1_1") (pintype "passive"))
    )
    (net (code "109") (name "/HALL15_~{SLEEP}") (class "Default")
      (node (ref "HALL15") (pin "3") (pinfunction "3_3") (pintype "passive"))
      (node (ref "SHIFT_1") (pin "7") (pinfunction "QH_7") (pintype "tri_state"))
    )
    (net (code "110") (name "/LED_GRN") (class "Default")
      (node (ref "R2") (pin "2") (pinfunction "2_2") (pintype "passive"))
      (node (ref "U1") (pin "26") (pinfunction "PC3(ADC3)_26") (pintype "bidirectional"))
    )
    (net (code "111") (name "/LED_RED") (class "Default")
      (node (ref "R1") (pin "2") (pinfunction "2_2") (pintype "passive"))
      (node (ref "U1") (pin "2") (pinfunction "PD4(XCK/T0)_2") (pintype "bidirectional"))
    )
    (net (code "112") (name "/MISO") (class "Default")
      (node (ref "J1") (pin "1") (pinfunction "1_1") (pintype "passive"))
      (node (ref "U$1") (pin "MISO7") (pinfunction "DATA_OUT_MISO_MISO7") (pintype "output"))
      (node (ref "U1") (pin "16") (pinfunction "PB4(MISO)_16") (pintype "bidirectional"))
    )
    (net (code "113") (name "/MOSI") (class "Default")
      (node (ref "J1") (pin "4") (pinfunction "4_4") (pintype "passive"))
      (node (ref "SHIFT_0") (pin "14") (pinfunction "SER_14") (pintype "input"))
      (node (ref "U$1") (pin "MOSI3") (pinfunction "DATA_IN_MOSI_MOSI3") (pintype "input"))
      (node (ref "U1") (pin "15") (pinfunction "PB3(MOSI/OC2)_15") (pintype "bidirectional"))
    )
    (net (code "114") (name "/MUX_S0") (class "Default")
      (node (ref "U$2") (pin "10") (pinfunction "S0_10") (pintype "input"))
      (node (ref "U1") (pin "13") (pinfunction "PB1(OC1A)_13") (pintype "bidirectional"))
    )
    (net (code "115") (name "/MUX_S1") (class "Default")
      (node (ref "U$2") (pin "11") (pinfunction "S1_11") (pintype "input"))
      (node (ref "U1") (pin "9") (pinfunction "PD5(T1)_9") (pintype "bidirectional"))
    )
    (net (code "116") (name "/MUX_S2") (class "Default")
      (node (ref "U$2") (pin "14") (pinfunction "S2_14") (pintype "input"))
      (node (ref "U1") (pin "10") (pinfunction "PD6(AIN0)_10") (pintype "bidirectional"))
    )
    (net (code "117") (name "/MUX_S3") (class "Default")
      (node (ref "U$2") (pin "13") (pinfunction "S3_13") (pintype "input"))
      (node (ref "U1") (pin "11") (pinfunction "PD7(AIN1)_11") (pintype "bidirectional"))
    )
    (net (code "118") (name "/MUX_~{EN}") (class "Default")
      (node (ref "R28") (pin "1") (pinfunction "1_1") (pintype "passive"))
      (node (ref "U$2") (pin "15") (pinfunction "~{E}_15") (pintype "input"))
      (node (ref "U1") (pin "12") (pinfunction "PB0(ICP)_12") (pintype "bidirectional"))
    )
    (net (code "119") (name "/RESET") (class "Default")
      (node (ref "C5") (pin "2") (pinfunction "2_2") (pintype "passive"))
      (node (ref "J1") (pin "5") (pinfunction "5_5") (pintype "passive"))
      (node (ref "R6") (pin "1") (pinfunction "1_1") (pintype "passive"))
      (node (ref "RESET") (pin "S$1") (pinfunction "S1_S$1") (pintype "passive"))
      (node (ref "U$3") (pin "1") (pinfunction "P$1_1") (pintype "bidirectional"))
      (node (ref "U1") (pin "29") (pinfunction "PC6(/RESET)_29") (pintype "bidirectional"))
    )
    (net (code "120") (name "/SCK") (class "Default")
      (node (ref "J1") (pin "3") (pinfunction "3_3") (pintype "passive"))
      (node (ref "SHIFT_0") (pin "11") (pinfunction "SRCLK_11") (pintype "input"))
      (node (ref "SHIFT_1") (pin "11") (pinfunction "SRCLK_11") (pintype "input"))
      (node (ref "U$1") (pin "SCK5") (pinfunction "SCLK_SCK5") (pintype "input"))
      (node (ref "U1") (pin "17") (pinfunction "PB5(SCK)_17") (pintype "bidirectional"))
    )
    (net (code "121") (name "/SCL") (class "Default")
      (node (ref "DS3231M") (pin "8") (pinfunction "P$8_SCL_8") (pintype "bidirectional"))
      (node (ref "I2C_HEADER") (pin "3") (pinfunction "3_3") (pintype "passive"))
      (node (ref "R7") (pin "1") (pinfunction "1_1") (pintype "passive"))
      (node (ref "U1") (pin "28") (pinfunction "PC5(ADC5/SCL)_28") (pintype "bidirectional"))
    )
    (net (code "122") (name "/SDA") (class "Default")
      (node (ref "DS3231M") (pin "7") (pinfunction "P$7_SDA_7") (pintype "bidirectional"))
      (node (ref "I2C_HEADER") (pin "4") (pinfunction "4_4") (pintype "passive"))
      (node (ref "R8") (pin "1") (pinfunction "1_1") (pintype "passive"))
      (node (ref "U1") (pin "27") (pinfunction "PC4(ADC4/SDA)_27") (pintype "bidirectional"))
    )
    (net (code "123") (name "/SHIFT_CLEAR") (class "Default")
      (node (ref "R14") (pin "1") (pinfunction "1_1") (pintype "passive"))
      (node (ref "SHIFT_0") (pin "10") (pinfunction "~{SRCLR}_10") (pintype "input"))
      (node (ref "SHIFT_1") (pin "10") (pinfunction "~{SRCLR}_10") (pintype "input"))
      (node (ref "U1") (pin "24") (pinfunction "PC1(ADC1)_24") (pintype "bidirectional"))
    )
    (net (code "124") (name "/TO_FTDI_RX") (class "Default")
      (node (ref "JP1") (pin "5") (pinfunction "5_5") (pintype "passive"))
      (node (ref "U1") (pin "31") (pinfunction "PD1(TXD)_31") (pintype "bidirectional"))
    )
    (net (code "125") (name "/TO_FTDI_TX") (class "Default")
      (node (ref "JP1") (pin "4") (pinfunction "4_4") (pintype "passive"))
      (node (ref "U1") (pin "30") (pinfunction "PD0(RXD)_30") (pintype "bidirectional"))
    )
    (net (code "126") (name "/VBAT") (class "Default")
      (node (ref "CR1220_BATTERY") (pin "P$1") (pinfunction "VBAT_P$1") (pintype "power_in"))
      (node (ref "CR1220_BATTERY") (pin "P$2") (pinfunction "P$2_P$2") (pintype "power_in"))
      (node (ref "DS3231M") (pin "6") (pinfunction "P$6_VBAT_6") (pintype "bidirectional"))
    )
    (net (code "127") (name "/VRAW") (class "Default")
      (node (ref "C1") (pin "+") (pinfunction "+_+") (pintype "passive"))
      (node (ref "MCP1700T-3302") (pin "3") (pinfunction "VIN_3") (pintype "input"))
      (node (ref "P-FET") (pin "2") (pinfunction "S_2") (pintype "passive"))
      (node (ref "R33") (pin "2") (pinfunction "2_2") (pintype "passive"))
      (node (ref "X1") (pin "2") (pinfunction "S_2") (pintype "passive"))
    )
    (net (code "128") (name "/~{SLEEP0}") (class "Default")
      (node (ref "A139_HALL0") (pin "P$5") (pinfunction "P$5_P$5") (pintype "bidirectional"))
      (node (ref "R16") (pin "2") (pinfunction "2_2") (pintype "passive"))
    )
    (net (code "129") (name "/~{SLEEP1}") (class "Default")
      (node (ref "A139_HALL1") (pin "P$5") (pinfunction "P$5_P$5") (pintype "bidirectional"))
      (node (ref "R11") (pin "2") (pinfunction "2_2") (pintype "passive"))
    )
    (net (code "130") (name "/~{SLEEP2}") (class "Default")
      (node (ref "A139_HALL2") (pin "P$5") (pinfunction "P$5_P$5") (pintype "bidirectional"))
      (node (ref "R10") (pin "2") (pinfunction "2_2") (pintype "passive"))
    )
    (net (code "131") (name "/~{SLEEP3}") (class "Default")
      (node (ref "A139_HALL3") (pin "P$5") (pinfunction "P$5_P$5") (pintype "bidirectional"))
      (node (ref "R12") (pin "2") (pinfunction "2_2") (pintype "passive"))
    )
    (net (code "132") (name "/~{SLEEP4}") (class "Default")
      (node (ref "A139_HALL4") (pin "P$5") (pinfunction "P$5_P$5") (pintype "bidirectional"))
      (node (ref "R13") (pin "2") (pinfunction "2_2") (pintype "passive"))
    )
    (net (code "133") (name "/~{SLEEP5}") (class "Default")
      (node (ref "A139_HALL5") (pin "P$5") (pinfunction "P$5_P$5") (pintype "bidirectional"))
      (node (ref "R17") (pin "2") (pinfunction "2_2") (pintype "passive"))
    )
    (net (code "134") (name "/~{SLEEP6}") (class "Default")
      (node (ref "A139_HALL6") (pin "P$5") (pinfunction "P$5_P$5") (pintype "bidirectional"))
      (node (ref "R18") (pin "2") (pinfunction "2_2") (pintype "passive"))
    )
    (net (code "135") (name "/~{SLEEP7}") (class "Default")
      (node (ref "A139_HALL7") (pin "P$5") (pinfunction "P$5_P$5") (pintype "bidirectional"))
      (node (ref "R19") (pin "2") (pinfunction "2_2") (pintype "passive"))
    )
    (net (code "136") (name "/~{SLEEP8}") (class "Default")
      (node (ref "A139_HALL8") (pin "P$5") (pinfunction "P$5_P$5") (pintype "bidirectional"))
      (node (ref "R24") (pin "2") (pinfunction "2_2") (pintype "passive"))
    )
    (net (code "137") (name "/~{SLEEP9}") (class "Default")
      (node (ref "A139_HALL9") (pin "P$5") (pinfunction "P$5_P$5") (pintype "bidirectional"))
      (node (ref "R20") (pin "2") (pinfunction "2_2") (pintype "passive"))
    )
    (net (code "138") (name "/~{SLEEP10}") (class "Default")
      (node (ref "A139_HALL10") (pin "P$5") (pinfunction "P$5_P$5") (pintype "bidirectional"))
      (node (ref "R21") (pin "2") (pinfunction "2_2") (pintype "passive"))
    )
    (net (code "139") (name "/~{SLEEP11}") (class "Default")
      (node (ref "A139_HALL11") (pin "P$5") (pinfunction "P$5_P$5") (pintype "bidirectional"))
      (node (ref "R22") (pin "2") (pinfunction "2_2") (pintype "passive"))
    )
    (net (code "140") (name "/~{SLEEP12}") (class "Default")
      (node (ref "A139_HALL12") (pin "P$5") (pinfunction "P$5_P$5") (pintype "bidirectional"))
      (node (ref "R23") (pin "2") (pinfunction "2_2") (pintype "passive"))
    )
    (net (code "141") (name "/~{SLEEP13}") (class "Default")
      (node (ref "A139_HALL13") (pin "P$5") (pinfunction "P$5_P$5") (pintype "bidirectional"))
      (node (ref "R25") (pin "2") (pinfunction "2_2") (pintype "passive"))
    )
    (net (code "142") (name "/~{SLEEP14}") (class "Default")
      (node (ref "A139_HALL14") (pin "P$5") (pinfunction "P$5_P$5") (pintype "bidirectional"))
      (node (ref "R26") (pin "2") (pinfunction "2_2") (pintype "passive"))
    )
    (net (code "143") (name "/~{SLEEP15}") (class "Default")
      (node (ref "A139_HALL15") (pin "P$5") (pinfunction "P$5_P$5") (pintype "bidirectional"))
      (node (ref "R27") (pin "2") (pinfunction "2_2") (pintype "passive"))
    )
    (net (code "144") (name "GND") (class "Default")
      (node (ref "1") (pin "S$1") (pinfunction "S1_S$1") (pintype "passive"))
      (node (ref "2") (pin "S$1") (pinfunction "S1_S$1") (pintype "passive"))
      (node (ref "BJT") (pin "2") (pinfunction "E_2") (pintype "passive"))
      (node (ref "C1") (pin "-") (pinfunction "-_-") (pintype "passive"))
      (node (ref "C2") (pin "-") (pinfunction "-_-") (pintype "passive"))
      (node (ref "C3") (pin "2") (pinfunction "2_2") (pintype "passive"))
      (node (ref "C4") (pin "2") (pinfunction "2_2") (pintype "passive"))
      (node (ref "C6") (pin "2") (pinfunction "2_2") (pintype "passive"))
      (node (ref "C7") (pin "2") (pinfunction "2_2") (pintype "passive"))
      (node (ref "C8") (pin "2") (pinfunction "2_2") (pintype "passive"))
      (node (ref "C9") (pin "2") (pinfunction "2_2") (pintype "passive"))
      (node (ref "CR1220_BATTERY") (pin "GND") (pinfunction "GND_GND") (pintype "power_in"))
      (node (ref "DS3231M") (pin "5") (pinfunction "P$5_GND_5") (pintype "power_in"))
      (node (ref "GROUND_CON") (pin "1") (pinfunction "P$1_1") (pintype "bidirectional"))
      (node (ref "I2C_HEADER") (pin "2") (pinfunction "2_2") (pintype "passive"))
      (node (ref "J1") (pin "6") (pinfunction "6_6") (pintype "passive"))
      (node (ref "JP1") (pin "1") (pinfunction "1_1") (pintype "passive"))
      (node (ref "JP1") (pin "2") (pinfunction "2_2") (pintype "passive"))
      (node (ref "LED1") (pin "C") (pinfunction "C_C") (pintype "passive"))
      (node (ref "LED2") (pin "C") (pinfunction "C_C") (pintype "passive"))
      (node (ref "MCP1700T-3302") (pin "1") (pinfunction "GND_1") (pintype "passive"))
      (node (ref "R29") (pin "1") (pinfunction "1_1") (pintype "passive"))
      (node (ref "R3") (pin "1") (pinfunction "1_1") (pintype "passive"))
      (node (ref "R32") (pin "1") (pinfunction "1_1") (pintype "passive"))
      (node (ref "RESET") (pin "P$1") (pinfunction "P1_P$1") (pintype "passive"))
      (node (ref "SHIFT_0") (pin "13") (pinfunction "~{OE}_13") (pintype "input"))
      (node (ref "SHIFT_0") (pin "8") (pinfunction "GND_8") (pintype "power_in"))
      (node (ref "SHIFT_1") (pin "13") (pinfunction "~{OE}_13") (pintype "input"))
      (node (ref "SHIFT_1") (pin "8") (pinfunction "GND_8") (pintype "power_in"))
      (node (ref "U$1") (pin "GND6") (pinfunction "VSS_GND_GND6") (pintype "power_in"))
      (node (ref "U$1") (pin "MNT1") (pinfunction "GND1_MNT1") (pintype "power_in"))
      (node (ref "U$1") (pin "MNT2") (pinfunction "GND2_MNT2") (pintype "power_in"))
      (node (ref "U$1") (pin "MNT3") (pinfunction "GND3_MNT3") (pintype "power_in"))
      (node (ref "U$1") (pin "MNT4") (pinfunction "GND4_MNT4") (pintype "power_in"))
      (node (ref "U$2") (pin "12") (pinfunction "GND_12") (pintype "power_in"))
      (node (ref "U$4") (pin "1") (pinfunction "P$1_1") (pintype "bidirectional"))
      (node (ref "U$7") (pin "1") (pinfunction "P$1_1") (pintype "bidirectional"))
      (node (ref "U$9") (pin "1") (pinfunction "P$1_1") (pintype "bidirectional"))
      (node (ref "U1") (pin "3") (pinfunction "GND_3") (pintype "bidirectional"))
      (node (ref "U1") (pin "5") (pinfunction "GND_5") (pintype "bidirectional"))
      (node (ref "X1") (pin "1") (pinfunction "S_1") (pintype "passive"))
    )
    (net (code "145") (name "Net-(BJT-B)") (class "Default")
      (node (ref "BJT") (pin "1") (pinfunction "B_1") (pintype "passive"))
      (node (ref "R31") (pin "2") (pinfunction "2_2") (pintype "passive"))
    )
    (net (code "146") (name "Net-(LED1-PadA)") (class "Default")
      (node (ref "LED1") (pin "A") (pinfunction "A_A") (pintype "passive"))
      (node (ref "R1") (pin "1") (pinfunction "1_1") (pintype "passive"))
    )
    (net (code "147") (name "Net-(LED2-PadA)") (class "Default")
      (node (ref "LED2") (pin "A") (pinfunction "A_A") (pintype "passive"))
      (node (ref "R2") (pin "1") (pinfunction "1_1") (pintype "passive"))
    )
    (net (code "148") (name "Net-(P-FET-D)") (class "Default")
      (node (ref "P-FET") (pin "3") (pinfunction "D_3") (pintype "passive"))
      (node (ref "R30") (pin "2") (pinfunction "2_2") (pintype "passive"))
    )
    (net (code "149") (name "Net-(SHIFT_0-QH*)") (class "Default")
      (node (ref "SHIFT_0") (pin "9") (pinfunction "QH*_9") (pintype "tri_state"))
      (node (ref "SHIFT_1") (pin "14") (pinfunction "SER_14") (pintype "input"))
    )
    (net (code "150") (name "Net-(U$1-DAT1_NC)") (class "Default")
      (node (ref "R5") (pin "1") (pinfunction "1_1") (pintype "passive"))
      (node (ref "U$1") (pin "NC1") (pinfunction "DAT1_NC_NC1") (pintype "bidirectional"))
    )
    (net (code "151") (name "Net-(U$1-DAT2_RES)") (class "Default")
      (node (ref "R4") (pin "1") (pinfunction "1_1") (pintype "passive"))
      (node (ref "U$1") (pin "RES8") (pinfunction "DAT2_RES_RES8") (pintype "bidirectional"))
    )
    (net (code "152") (name "VCC") (class "Default")
      (node (ref "C2") (pin "+") (pinfunction "+_+") (pintype "passive"))
      (node (ref "C3") (pin "1") (pinfunction "1_1") (pintype "passive"))
      (node (ref "C4") (pin "1") (pinfunction "1_1") (pintype "passive"))
      (node (ref "C6") (pin "1") (pinfunction "1_1") (pintype "passive"))
      (node (ref "C7") (pin "1") (pinfunction "1_1") (pintype "passive"))
      (node (ref "C8") (pin "1") (pinfunction "1_1") (pintype "passive"))
      (node (ref "C9") (pin "1") (pinfunction "1_1") (pintype "passive"))
      (node (ref "DS3231M") (pin "2") (pinfunction "P$2_VCC_2") (pintype "power_in"))
      (node (ref "HALL0") (pin "1") (pinfunction "1_1") (pintype "passive"))
      (node (ref "HALL1") (pin "1") (pinfunction "1_1") (pintype "passive"))
      (node (ref "HALL10") (pin "1") (pinfunction "1_1") (pintype "passive"))
      (node (ref "HALL11") (pin "1") (pinfunction "1_1") (pintype "passive"))
      (node (ref "HALL12") (pin "1") (pinfunction "1_1") (pintype "passive"))
      (node (ref "HALL13") (pin "1") (pinfunction "1_1") (pintype "passive"))
      (node (ref "HALL14") (pin "1") (pinfunction "1_1") (pintype "passive"))
      (node (ref "HALL15") (pin "1") (pinfunction "1_1") (pintype "passive"))
      (node (ref "HALL2") (pin "1") (pinfunction "1_1") (pintype "passive"))
      (node (ref "HALL3") (pin "1") (pinfunction "1_1") (pintype "passive"))
      (node (ref "HALL4") (pin "1") (pinfunction "1_1") (pintype "passive"))
      (node (ref "HALL5") (pin "1") (pinfunction "1_1") (pintype "passive"))
      (node (ref "HALL6") (pin "1") (pinfunction "1_1") (pintype "passive"))
      (node (ref "HALL7") (pin "1") (pinfunction "1_1") (pintype "passive"))
      (node (ref "HALL8") (pin "1") (pinfunction "1_1") (pintype "passive"))
      (node (ref "HALL9") (pin "1") (pinfunction "1_1") (pintype "passive"))
      (node (ref "I2C_HEADER") (pin "1") (pinfunction "1_1") (pintype "passive"))
      (node (ref "INDUCTOR") (pin "P$2") (pinfunction "2_P$2") (pintype "passive"))
      (node (ref "J1") (pin "2") (pinfunction "2_2") (pintype "passive"))
      (node (ref "JP1") (pin "3") (pinfunction "3_3") (pintype "passive"))
      (node (ref "MCP1700T-3302") (pin "2") (pinfunction "VOUT_2") (pintype "output"))
      (node (ref "R14") (pin "2") (pinfunction "2_2") (pintype "passive"))
      (node (ref "R15") (pin "2") (pinfunction "2_2") (pintype "passive"))
      (node (ref "R28") (pin "2") (pinfunction "2_2") (pintype "passive"))
      (node (ref "R4") (pin "2") (pinfunction "2_2") (pintype "passive"))
      (node (ref "R5") (pin "2") (pinfunction "2_2") (pintype "passive"))
      (node (ref "R6") (pin "2") (pinfunction "2_2") (pintype "passive"))
      (node (ref "R7") (pin "2") (pinfunction "2_2") (pintype "passive"))
      (node (ref "R8") (pin "2") (pinfunction "2_2") (pintype "passive"))
      (node (ref "R9") (pin "2") (pinfunction "2_2") (pintype "passive"))
      (node (ref "SHIFT_0") (pin "16") (pinfunction "VCC_16") (pintype "power_in"))
      (node (ref "SHIFT_1") (pin "16") (pinfunction "VCC_16") (pintype "power_in"))
      (node (ref "U$1") (pin "VDD4") (pinfunction "VDD_VDD4") (pintype "power_in"))
      (node (ref "U$2") (pin "24") (pinfunction "VCC_24") (pintype "power_in"))
      (node (ref "U1") (pin "4") (pinfunction "VCC_4") (pintype "bidirectional"))
      (node (ref "U1") (pin "6") (pinfunction "VCC_6") (pintype "bidirectional"))
    )
    (net (code "153") (name "unconnected-(1-PadP)") (class "Default")
      (node (ref "1") (pin "P") (pinfunction "P_P") (pintype "passive"))
    )
    (net (code "154") (name "unconnected-(1-PadS)") (class "Default")
      (node (ref "1") (pin "S") (pinfunction "S_S") (pintype "passive"))
    )
    (net (code "155") (name "unconnected-(2-PadP)") (class "Default")
      (node (ref "2") (pin "P") (pinfunction "P_P") (pintype "passive"))
    )
    (net (code "156") (name "unconnected-(2-PadS)") (class "Default")
      (node (ref "2") (pin "S") (pinfunction "S_S") (pintype "passive"))
    )
    (net (code "157") (name "unconnected-(DS3231M-P$3_INT-Pad3)") (class "Default")
      (node (ref "DS3231M") (pin "3") (pinfunction "P$3_INT_3") (pintype "bidirectional"))
    )
    (net (code "158") (name "unconnected-(DS3231M-P$4_RST-Pad4)") (class "Default")
      (node (ref "DS3231M") (pin "4") (pinfunction "P$4_RST_4") (pintype "bidirectional"))
    )
    (net (code "159") (name "unconnected-(RESET-PadP)") (class "Default")
      (node (ref "RESET") (pin "P") (pinfunction "P_P") (pintype "passive"))
    )
    (net (code "160") (name "unconnected-(RESET-PadS)") (class "Default")
      (node (ref "RESET") (pin "S") (pinfunction "S_S") (pintype "passive"))
    )
    (net (code "161") (name "unconnected-(SHIFT_1-QH*-Pad9)") (class "Default")
      (node (ref "SHIFT_1") (pin "9") (pinfunction "QH*_9") (pintype "tri_state"))
    )
    (net (code "162") (name "unconnected-(U$1-CARD_DETECT-PadCARD_DETECT1)") (class "Default")
      (node (ref "U$1") (pin "CARD_DETECT1") (pinfunction "CARD_DETECT_CARD_DETECT1") (pintype "passive"))
    )
    (net (code "163") (name "unconnected-(U$1-CARD_DETECT1-PadCARD_DETECT2)") (class "Default")
      (node (ref "U$1") (pin "CARD_DETECT2") (pinfunction "CARD_DETECT1_CARD_DETECT2") (pintype "passive"))
    )
    (net (code "164") (name "unconnected-(U1-PB7(XTAL2{slash}TOSC2)-Pad8)") (class "Default")
      (node (ref "U1") (pin "8") (pinfunction "PB7(XTAL2/TOSC2)_8") (pintype "bidirectional"))
    )
  )
)
